# Page_B_SignalInput.net
KiCad netlist of a schematic drawn in Altium Designer
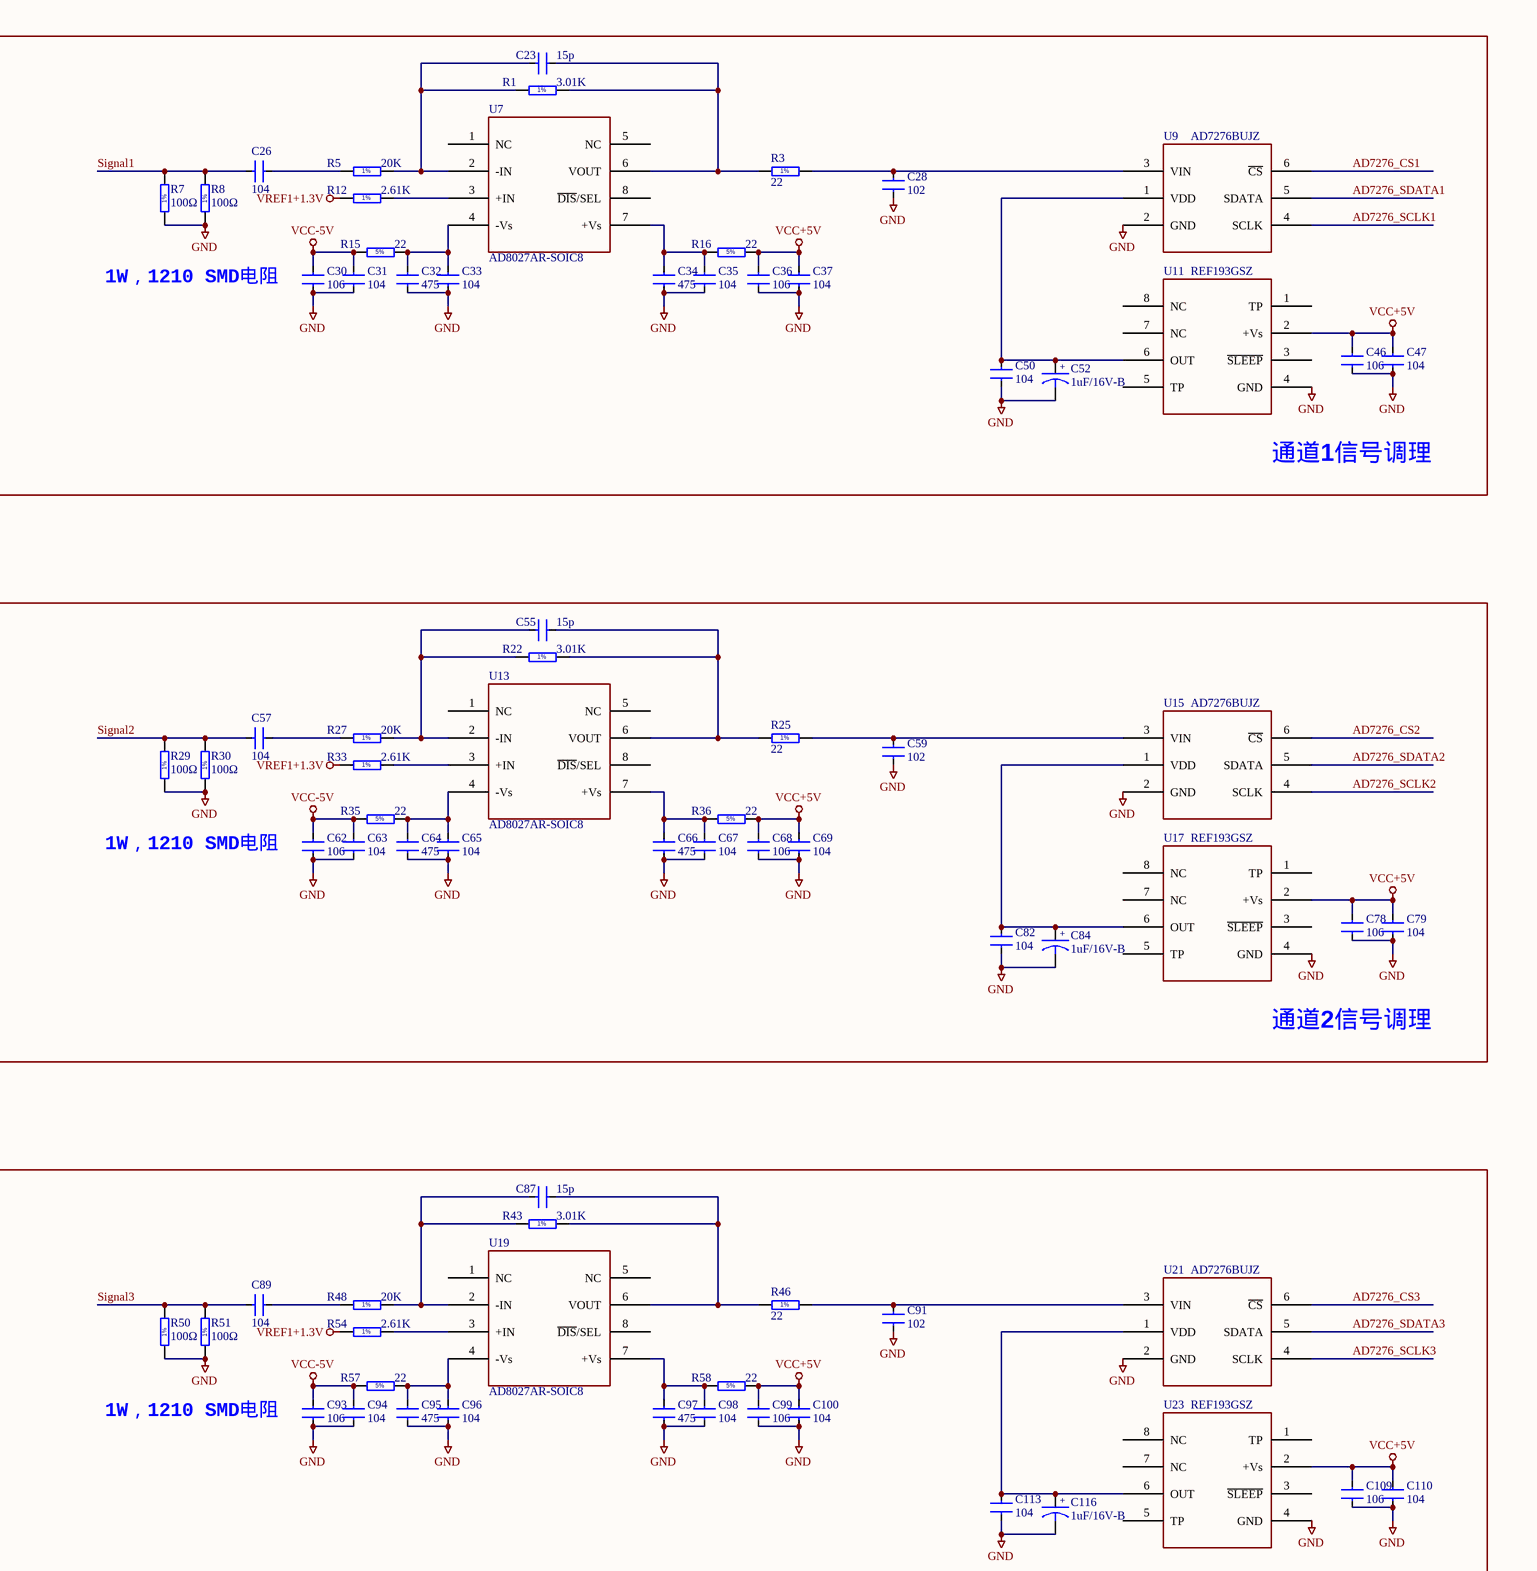
[diagram p0: Page B_SignalInput.SchDoc, top left]
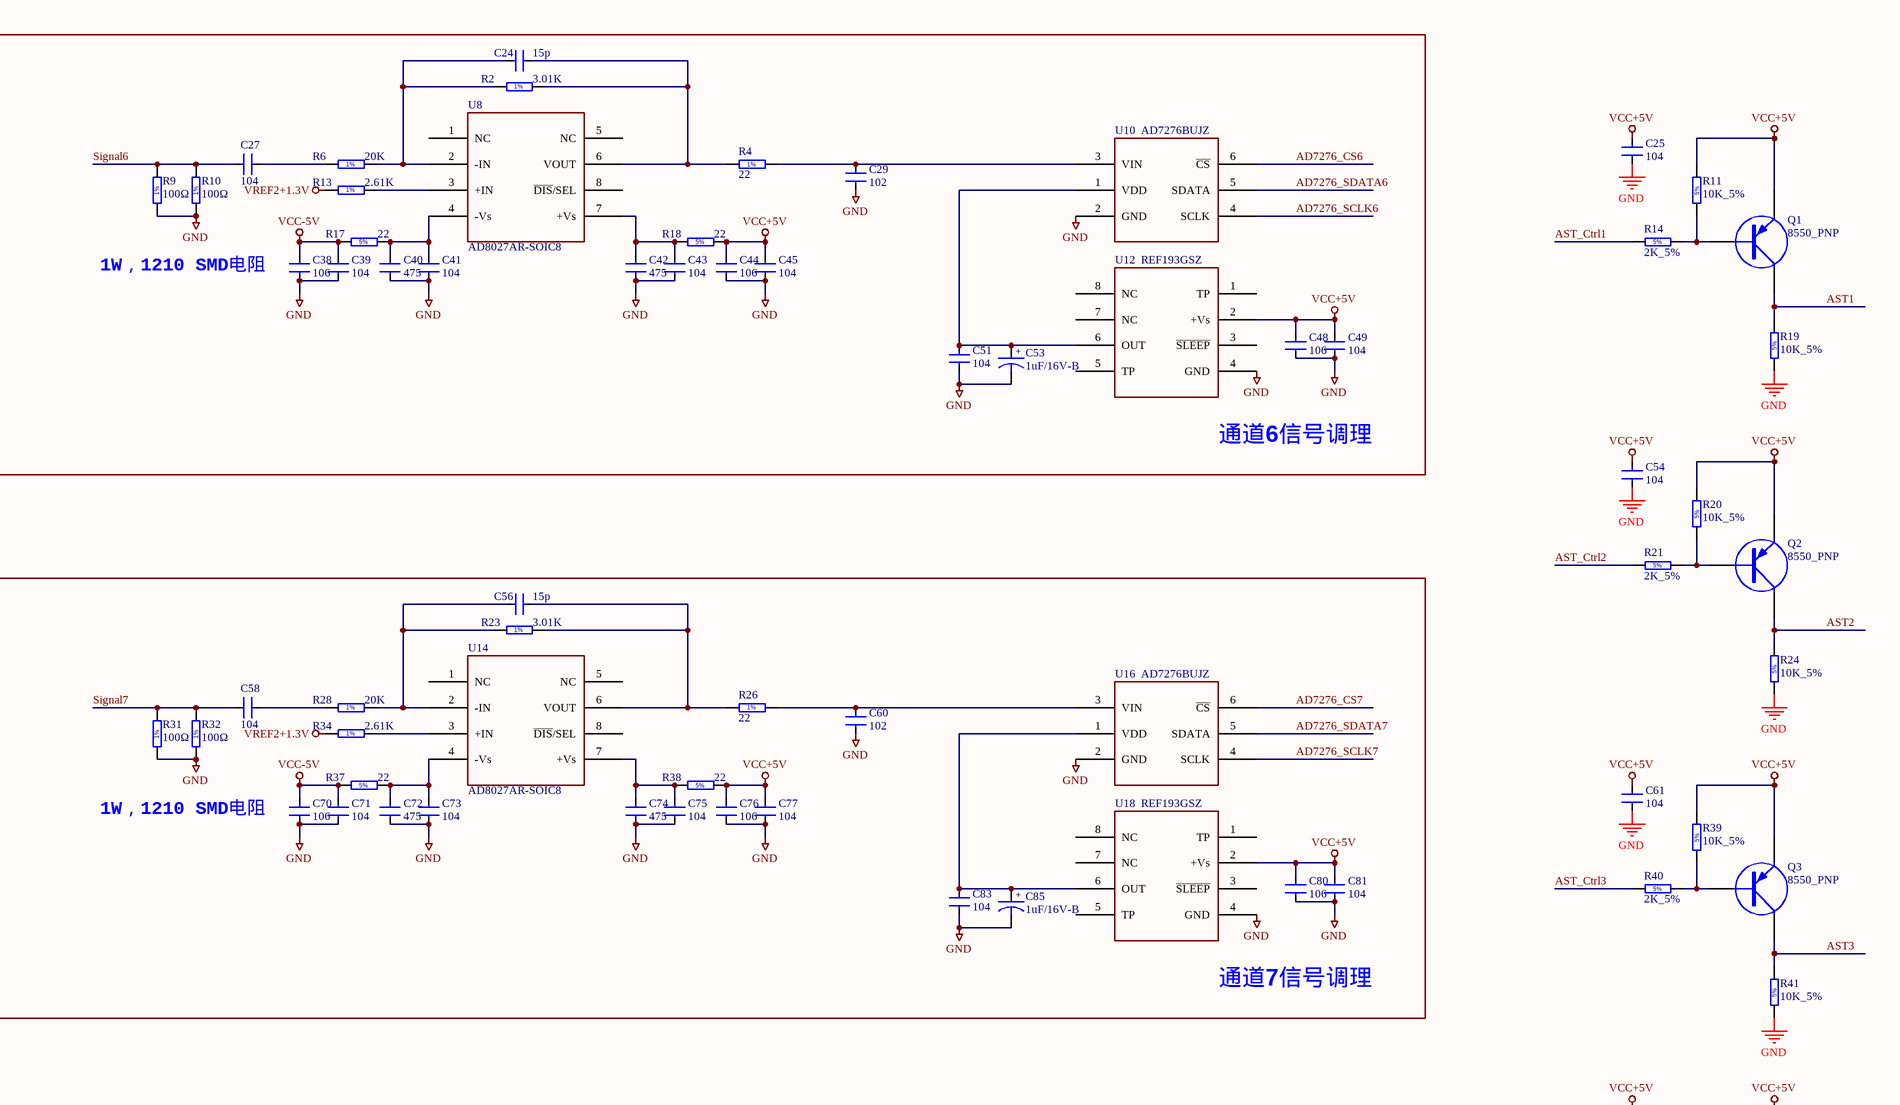
[diagram p1: Page B_SignalInput.SchDoc, top right]
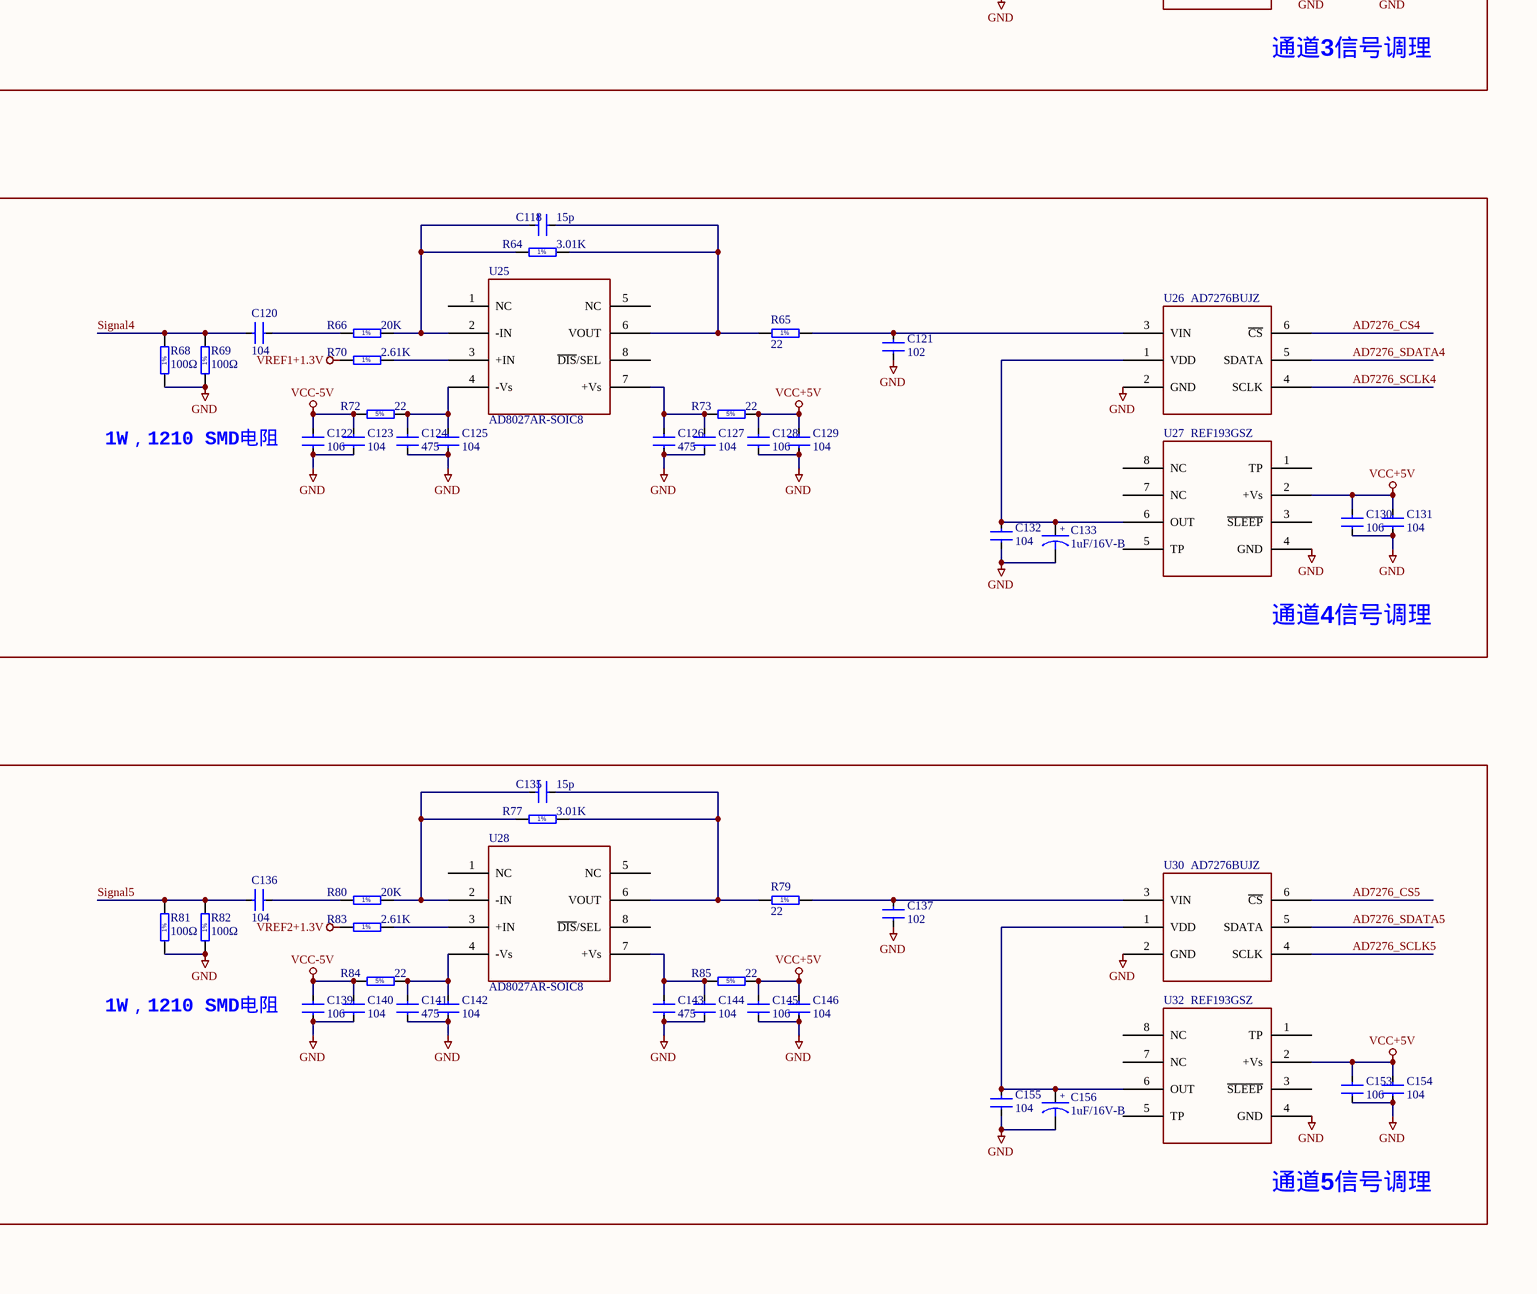
[diagram p2: Page B_SignalInput.SchDoc, bottom left]
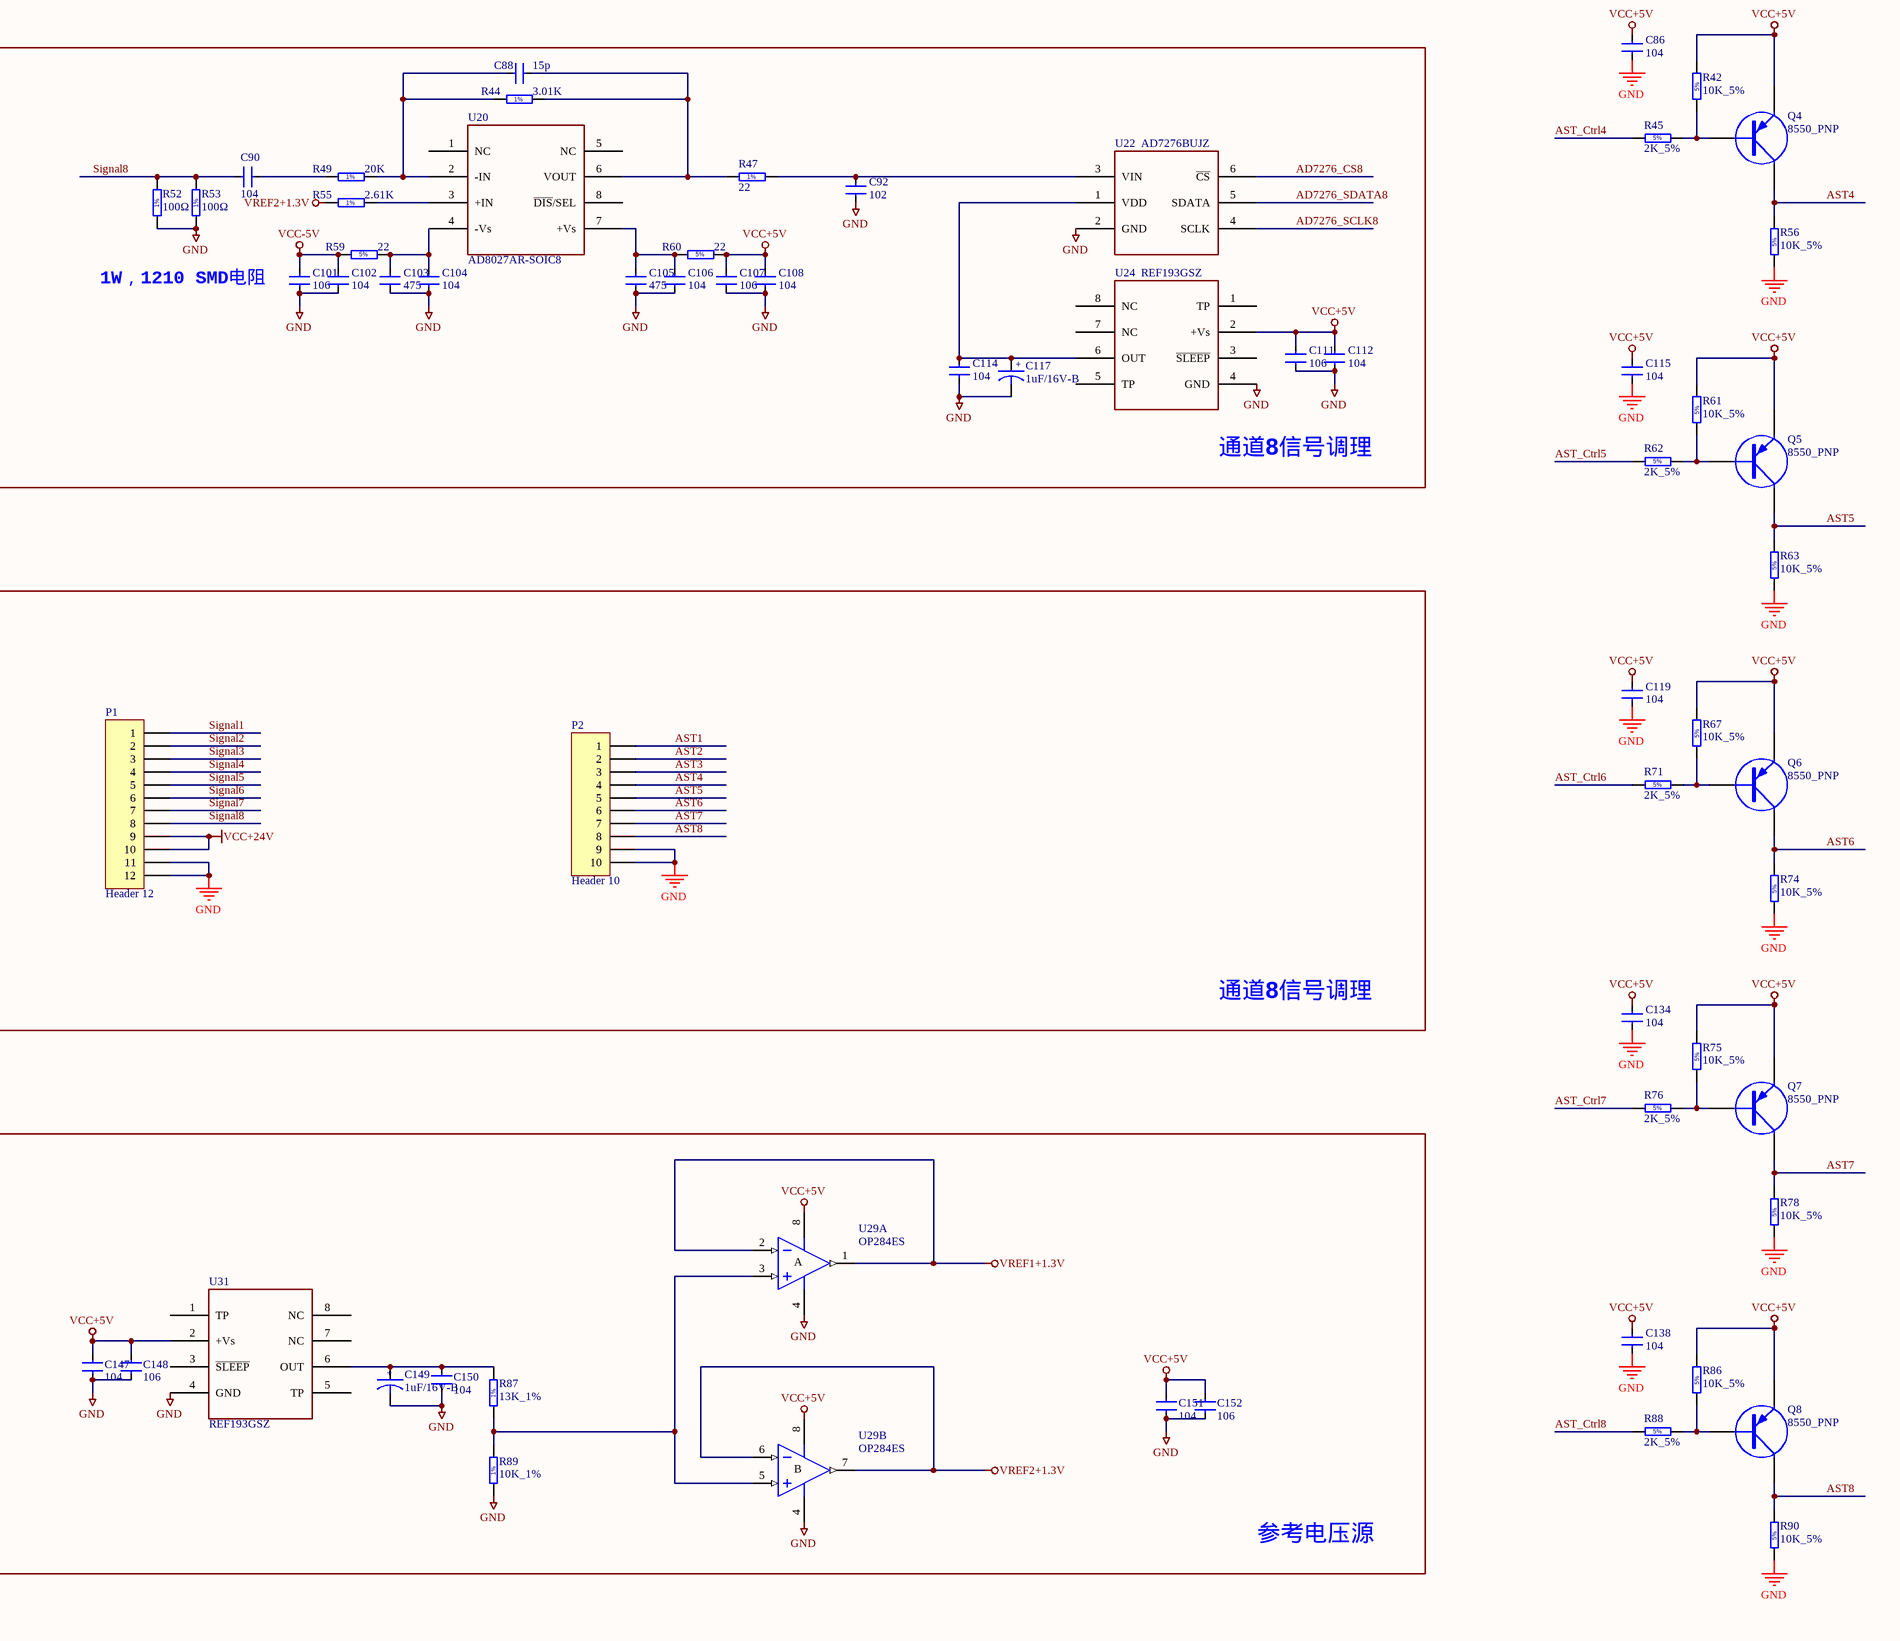
[diagram p3: Page B_SignalInput.SchDoc, bottom right]

(export (version "E")
  (design (tool "Eeschema 10.0.6"))
  (components
    (comp (ref "C23")
      (value "15p")
      (footprint "0603C")
      (description "C-X5R/X7R")
      (libsource (lib "贴片电阻电容") (part "C-X5R/X7R"))
    )
    (comp (ref "C24")
      (value "15p")
      (footprint "0603C")
      (description "C-X5R/X7R")
      (libsource (lib "贴片电阻电容") (part "C-X5R/X7R"))
    )
    (comp (ref "C25")
      (value "104")
      (footprint "0603C")
      (description "C-X5R/X7R")
      (libsource (lib "贴片电阻电容") (part "C-X5R/X7R"))
    )
    (comp (ref "C26")
      (value "104")
      (footprint "0603C")
      (description "C-X5R/X7R")
      (libsource (lib "贴片电阻电容") (part "C-X5R/X7R"))
    )
    (comp (ref "C27")
      (value "104")
      (footprint "0603C")
      (description "C-X5R/X7R")
      (libsource (lib "贴片电阻电容") (part "C-X5R/X7R"))
    )
    (comp (ref "C28")
      (value "102")
      (footprint "0603C")
      (description "C-X5R/X7R")
      (libsource (lib "贴片电阻电容") (part "C-X5R/X7R"))
    )
    (comp (ref "C29")
      (value "102")
      (footprint "0603C")
      (description "C-X5R/X7R")
      (libsource (lib "贴片电阻电容") (part "C-X5R/X7R"))
    )
    (comp (ref "C30")
      (value "106")
      (footprint "0603C")
      (description "C-X5R/X7R")
      (libsource (lib "贴片电阻电容") (part "C-X5R/X7R"))
    )
    (comp (ref "C31")
      (value "104")
      (footprint "0603C")
      (description "C-X5R/X7R")
      (libsource (lib "贴片电阻电容") (part "C-X5R/X7R"))
    )
    (comp (ref "C32")
      (value "475")
      (footprint "0603C")
      (description "C-X5R/X7R")
      (libsource (lib "贴片电阻电容") (part "C-X5R/X7R"))
    )
    (comp (ref "C33")
      (value "104")
      (footprint "0603C")
      (description "C-X5R/X7R")
      (libsource (lib "贴片电阻电容") (part "C-X5R/X7R"))
    )
    (comp (ref "C34")
      (value "475")
      (footprint "0603C")
      (description "C-X5R/X7R")
      (libsource (lib "贴片电阻电容") (part "C-X5R/X7R"))
    )
    (comp (ref "C35")
      (value "104")
      (footprint "0603C")
      (description "C-X5R/X7R")
      (libsource (lib "贴片电阻电容") (part "C-X5R/X7R"))
    )
    (comp (ref "C36")
      (value "106")
      (footprint "0603C")
      (description "C-X5R/X7R")
      (libsource (lib "贴片电阻电容") (part "C-X5R/X7R"))
    )
    (comp (ref "C37")
      (value "104")
      (footprint "0603C")
      (description "C-X5R/X7R")
      (libsource (lib "贴片电阻电容") (part "C-X5R/X7R"))
    )
    (comp (ref "C38")
      (value "106")
      (footprint "0603C")
      (description "C-X5R/X7R")
      (libsource (lib "贴片电阻电容") (part "C-X5R/X7R"))
    )
    (comp (ref "C39")
      (value "104")
      (footprint "0603C")
      (description "C-X5R/X7R")
      (libsource (lib "贴片电阻电容") (part "C-X5R/X7R"))
    )
    (comp (ref "C40")
      (value "475")
      (footprint "0603C")
      (description "C-X5R/X7R")
      (libsource (lib "贴片电阻电容") (part "C-X5R/X7R"))
    )
    (comp (ref "C41")
      (value "104")
      (footprint "0603C")
      (description "C-X5R/X7R")
      (libsource (lib "贴片电阻电容") (part "C-X5R/X7R"))
    )
    (comp (ref "C42")
      (value "475")
      (footprint "0603C")
      (description "C-X5R/X7R")
      (libsource (lib "贴片电阻电容") (part "C-X5R/X7R"))
    )
    (comp (ref "C43")
      (value "104")
      (footprint "0603C")
      (description "C-X5R/X7R")
      (libsource (lib "贴片电阻电容") (part "C-X5R/X7R"))
    )
    (comp (ref "C44")
      (value "106")
      (footprint "0603C")
      (description "C-X5R/X7R")
      (libsource (lib "贴片电阻电容") (part "C-X5R/X7R"))
    )
    (comp (ref "C45")
      (value "104")
      (footprint "0603C")
      (description "C-X5R/X7R")
      (libsource (lib "贴片电阻电容") (part "C-X5R/X7R"))
    )
    (comp (ref "C46")
      (value "106")
      (footprint "0603C")
      (description "C-X5R/X7R")
      (libsource (lib "贴片电阻电容") (part "C-X5R/X7R"))
    )
    (comp (ref "C47")
      (value "104")
      (footprint "0603C")
      (description "C-X5R/X7R")
      (libsource (lib "贴片电阻电容") (part "C-X5R/X7R"))
    )
    (comp (ref "C48")
      (value "106")
      (footprint "0603C")
      (description "C-X5R/X7R")
      (libsource (lib "贴片电阻电容") (part "C-X5R/X7R"))
    )
    (comp (ref "C49")
      (value "104")
      (footprint "0603C")
      (description "C-X5R/X7R")
      (libsource (lib "贴片电阻电容") (part "C-X5R/X7R"))
    )
    (comp (ref "C50")
      (value "104")
      (footprint "0603C")
      (description "C-X5R/X7R")
      (libsource (lib "贴片电阻电容") (part "C-X5R/X7R"))
    )
    (comp (ref "C51")
      (value "104")
      (footprint "0603C")
      (description "C-X5R/X7R")
      (libsource (lib "贴片电阻电容") (part "C-X5R/X7R"))
    )
    (comp (ref "C52") (value "1uF/16V-B") (footprint "TCC-B") (libsource (lib "钽电容") (part "10uF/16V-B")))
    (comp (ref "C53") (value "1uF/16V-B") (footprint "TCC-B") (libsource (lib "钽电容") (part "10uF/16V-B")))
    (comp (ref "C54")
      (value "104")
      (footprint "0603C")
      (description "C-X5R/X7R")
      (libsource (lib "贴片电阻电容") (part "C-X5R/X7R"))
    )
    (comp (ref "C55")
      (value "15p")
      (footprint "0603C")
      (description "C-X5R/X7R")
      (libsource (lib "贴片电阻电容") (part "C-X5R/X7R"))
    )
    (comp (ref "C56")
      (value "15p")
      (footprint "0603C")
      (description "C-X5R/X7R")
      (libsource (lib "贴片电阻电容") (part "C-X5R/X7R"))
    )
    (comp (ref "C57")
      (value "104")
      (footprint "0603C")
      (description "C-X5R/X7R")
      (libsource (lib "贴片电阻电容") (part "C-X5R/X7R"))
    )
    (comp (ref "C58")
      (value "104")
      (footprint "0603C")
      (description "C-X5R/X7R")
      (libsource (lib "贴片电阻电容") (part "C-X5R/X7R"))
    )
    (comp (ref "C59")
      (value "102")
      (footprint "0603C")
      (description "C-X5R/X7R")
      (libsource (lib "贴片电阻电容") (part "C-X5R/X7R"))
    )
    (comp (ref "C60")
      (value "102")
      (footprint "0603C")
      (description "C-X5R/X7R")
      (libsource (lib "贴片电阻电容") (part "C-X5R/X7R"))
    )
    (comp (ref "C61")
      (value "104")
      (footprint "0603C")
      (description "C-X5R/X7R")
      (libsource (lib "贴片电阻电容") (part "C-X5R/X7R"))
    )
    (comp (ref "C62")
      (value "106")
      (footprint "0603C")
      (description "C-X5R/X7R")
      (libsource (lib "贴片电阻电容") (part "C-X5R/X7R"))
    )
    (comp (ref "C63")
      (value "104")
      (footprint "0603C")
      (description "C-X5R/X7R")
      (libsource (lib "贴片电阻电容") (part "C-X5R/X7R"))
    )
    (comp (ref "C64")
      (value "475")
      (footprint "0603C")
      (description "C-X5R/X7R")
      (libsource (lib "贴片电阻电容") (part "C-X5R/X7R"))
    )
    (comp (ref "C65")
      (value "104")
      (footprint "0603C")
      (description "C-X5R/X7R")
      (libsource (lib "贴片电阻电容") (part "C-X5R/X7R"))
    )
    (comp (ref "C66")
      (value "475")
      (footprint "0603C")
      (description "C-X5R/X7R")
      (libsource (lib "贴片电阻电容") (part "C-X5R/X7R"))
    )
    (comp (ref "C67")
      (value "104")
      (footprint "0603C")
      (description "C-X5R/X7R")
      (libsource (lib "贴片电阻电容") (part "C-X5R/X7R"))
    )
    (comp (ref "C68")
      (value "106")
      (footprint "0603C")
      (description "C-X5R/X7R")
      (libsource (lib "贴片电阻电容") (part "C-X5R/X7R"))
    )
    (comp (ref "C69")
      (value "104")
      (footprint "0603C")
      (description "C-X5R/X7R")
      (libsource (lib "贴片电阻电容") (part "C-X5R/X7R"))
    )
    (comp (ref "C70")
      (value "106")
      (footprint "0603C")
      (description "C-X5R/X7R")
      (libsource (lib "贴片电阻电容") (part "C-X5R/X7R"))
    )
    (comp (ref "C71")
      (value "104")
      (footprint "0603C")
      (description "C-X5R/X7R")
      (libsource (lib "贴片电阻电容") (part "C-X5R/X7R"))
    )
    (comp (ref "C72")
      (value "475")
      (footprint "0603C")
      (description "C-X5R/X7R")
      (libsource (lib "贴片电阻电容") (part "C-X5R/X7R"))
    )
    (comp (ref "C73")
      (value "104")
      (footprint "0603C")
      (description "C-X5R/X7R")
      (libsource (lib "贴片电阻电容") (part "C-X5R/X7R"))
    )
    (comp (ref "C74")
      (value "475")
      (footprint "0603C")
      (description "C-X5R/X7R")
      (libsource (lib "贴片电阻电容") (part "C-X5R/X7R"))
    )
    (comp (ref "C75")
      (value "104")
      (footprint "0603C")
      (description "C-X5R/X7R")
      (libsource (lib "贴片电阻电容") (part "C-X5R/X7R"))
    )
    (comp (ref "C76")
      (value "106")
      (footprint "0603C")
      (description "C-X5R/X7R")
      (libsource (lib "贴片电阻电容") (part "C-X5R/X7R"))
    )
    (comp (ref "C77")
      (value "104")
      (footprint "0603C")
      (description "C-X5R/X7R")
      (libsource (lib "贴片电阻电容") (part "C-X5R/X7R"))
    )
    (comp (ref "C78")
      (value "106")
      (footprint "0603C")
      (description "C-X5R/X7R")
      (libsource (lib "贴片电阻电容") (part "C-X5R/X7R"))
    )
    (comp (ref "C79")
      (value "104")
      (footprint "0603C")
      (description "C-X5R/X7R")
      (libsource (lib "贴片电阻电容") (part "C-X5R/X7R"))
    )
    (comp (ref "C80")
      (value "106")
      (footprint "0603C")
      (description "C-X5R/X7R")
      (libsource (lib "贴片电阻电容") (part "C-X5R/X7R"))
    )
    (comp (ref "C81")
      (value "104")
      (footprint "0603C")
      (description "C-X5R/X7R")
      (libsource (lib "贴片电阻电容") (part "C-X5R/X7R"))
    )
    (comp (ref "C82")
      (value "104")
      (footprint "0603C")
      (description "C-X5R/X7R")
      (libsource (lib "贴片电阻电容") (part "C-X5R/X7R"))
    )
    (comp (ref "C83")
      (value "104")
      (footprint "0603C")
      (description "C-X5R/X7R")
      (libsource (lib "贴片电阻电容") (part "C-X5R/X7R"))
    )
    (comp (ref "C84") (value "1uF/16V-B") (footprint "TCC-B") (libsource (lib "钽电容") (part "10uF/16V-B")))
    (comp (ref "C85") (value "1uF/16V-B") (footprint "TCC-B") (libsource (lib "钽电容") (part "10uF/16V-B")))
    (comp (ref "C86")
      (value "104")
      (footprint "0603C")
      (description "C-X5R/X7R")
      (libsource (lib "贴片电阻电容") (part "C-X5R/X7R"))
    )
    (comp (ref "C87")
      (value "15p")
      (footprint "0603C")
      (description "C-X5R/X7R")
      (libsource (lib "贴片电阻电容") (part "C-X5R/X7R"))
    )
    (comp (ref "C88")
      (value "15p")
      (footprint "0603C")
      (description "C-X5R/X7R")
      (libsource (lib "贴片电阻电容") (part "C-X5R/X7R"))
    )
    (comp (ref "C89")
      (value "104")
      (footprint "0603C")
      (description "C-X5R/X7R")
      (libsource (lib "贴片电阻电容") (part "C-X5R/X7R"))
    )
    (comp (ref "C90")
      (value "104")
      (footprint "0603C")
      (description "C-X5R/X7R")
      (libsource (lib "贴片电阻电容") (part "C-X5R/X7R"))
    )
    (comp (ref "C91")
      (value "102")
      (footprint "0603C")
      (description "C-X5R/X7R")
      (libsource (lib "贴片电阻电容") (part "C-X5R/X7R"))
    )
    (comp (ref "C92")
      (value "102")
      (footprint "0603C")
      (description "C-X5R/X7R")
      (libsource (lib "贴片电阻电容") (part "C-X5R/X7R"))
    )
    (comp (ref "C93")
      (value "106")
      (footprint "0603C")
      (description "C-X5R/X7R")
      (libsource (lib "贴片电阻电容") (part "C-X5R/X7R"))
    )
    (comp (ref "C94")
      (value "104")
      (footprint "0603C")
      (description "C-X5R/X7R")
      (libsource (lib "贴片电阻电容") (part "C-X5R/X7R"))
    )
    (comp (ref "C95")
      (value "475")
      (footprint "0603C")
      (description "C-X5R/X7R")
      (libsource (lib "贴片电阻电容") (part "C-X5R/X7R"))
    )
    (comp (ref "C96")
      (value "104")
      (footprint "0603C")
      (description "C-X5R/X7R")
      (libsource (lib "贴片电阻电容") (part "C-X5R/X7R"))
    )
    (comp (ref "C97")
      (value "475")
      (footprint "0603C")
      (description "C-X5R/X7R")
      (libsource (lib "贴片电阻电容") (part "C-X5R/X7R"))
    )
    (comp (ref "C98")
      (value "104")
      (footprint "0603C")
      (description "C-X5R/X7R")
      (libsource (lib "贴片电阻电容") (part "C-X5R/X7R"))
    )
    (comp (ref "C99")
      (value "106")
      (footprint "0603C")
      (description "C-X5R/X7R")
      (libsource (lib "贴片电阻电容") (part "C-X5R/X7R"))
    )
    (comp (ref "C100")
      (value "104")
      (footprint "0603C")
      (description "C-X5R/X7R")
      (libsource (lib "贴片电阻电容") (part "C-X5R/X7R"))
    )
    (comp (ref "C101")
      (value "106")
      (footprint "0603C")
      (description "C-X5R/X7R")
      (libsource (lib "贴片电阻电容") (part "C-X5R/X7R"))
    )
    (comp (ref "C102")
      (value "104")
      (footprint "0603C")
      (description "C-X5R/X7R")
      (libsource (lib "贴片电阻电容") (part "C-X5R/X7R"))
    )
    (comp (ref "C103")
      (value "475")
      (footprint "0603C")
      (description "C-X5R/X7R")
      (libsource (lib "贴片电阻电容") (part "C-X5R/X7R"))
    )
    (comp (ref "C104")
      (value "104")
      (footprint "0603C")
      (description "C-X5R/X7R")
      (libsource (lib "贴片电阻电容") (part "C-X5R/X7R"))
    )
    (comp (ref "C105")
      (value "475")
      (footprint "0603C")
      (description "C-X5R/X7R")
      (libsource (lib "贴片电阻电容") (part "C-X5R/X7R"))
    )
    (comp (ref "C106")
      (value "104")
      (footprint "0603C")
      (description "C-X5R/X7R")
      (libsource (lib "贴片电阻电容") (part "C-X5R/X7R"))
    )
    (comp (ref "C107")
      (value "106")
      (footprint "0603C")
      (description "C-X5R/X7R")
      (libsource (lib "贴片电阻电容") (part "C-X5R/X7R"))
    )
    (comp (ref "C108")
      (value "104")
      (footprint "0603C")
      (description "C-X5R/X7R")
      (libsource (lib "贴片电阻电容") (part "C-X5R/X7R"))
    )
    (comp (ref "C109")
      (value "106")
      (footprint "0603C")
      (description "C-X5R/X7R")
      (libsource (lib "贴片电阻电容") (part "C-X5R/X7R"))
    )
    (comp (ref "C110")
      (value "104")
      (footprint "0603C")
      (description "C-X5R/X7R")
      (libsource (lib "贴片电阻电容") (part "C-X5R/X7R"))
    )
    (comp (ref "C111")
      (value "106")
      (footprint "0603C")
      (description "C-X5R/X7R")
      (libsource (lib "贴片电阻电容") (part "C-X5R/X7R"))
    )
    (comp (ref "C112")
      (value "104")
      (footprint "0603C")
      (description "C-X5R/X7R")
      (libsource (lib "贴片电阻电容") (part "C-X5R/X7R"))
    )
    (comp (ref "C113")
      (value "104")
      (footprint "0603C")
      (description "C-X5R/X7R")
      (libsource (lib "贴片电阻电容") (part "C-X5R/X7R"))
    )
    (comp (ref "C114")
      (value "104")
      (footprint "0603C")
      (description "C-X5R/X7R")
      (libsource (lib "贴片电阻电容") (part "C-X5R/X7R"))
    )
    (comp (ref "C115")
      (value "104")
      (footprint "0603C")
      (description "C-X5R/X7R")
      (libsource (lib "贴片电阻电容") (part "C-X5R/X7R"))
    )
    (comp (ref "C116") (value "1uF/16V-B") (footprint "TCC-B") (libsource (lib "钽电容") (part "10uF/16V-B")))
    (comp (ref "C117") (value "1uF/16V-B") (footprint "TCC-B") (libsource (lib "钽电容") (part "10uF/16V-B")))
    (comp (ref "C118")
      (value "15p")
      (footprint "0603C")
      (description "C-X5R/X7R")
      (libsource (lib "贴片电阻电容") (part "C-X5R/X7R"))
    )
    (comp (ref "C119")
      (value "104")
      (footprint "0603C")
      (description "C-X5R/X7R")
      (libsource (lib "贴片电阻电容") (part "C-X5R/X7R"))
    )
    (comp (ref "C120")
      (value "104")
      (footprint "0603C")
      (description "C-X5R/X7R")
      (libsource (lib "贴片电阻电容") (part "C-X5R/X7R"))
    )
    (comp (ref "C121")
      (value "102")
      (footprint "0603C")
      (description "C-X5R/X7R")
      (libsource (lib "贴片电阻电容") (part "C-X5R/X7R"))
    )
    (comp (ref "C122")
      (value "106")
      (footprint "0603C")
      (description "C-X5R/X7R")
      (libsource (lib "贴片电阻电容") (part "C-X5R/X7R"))
    )
    (comp (ref "C123")
      (value "104")
      (footprint "0603C")
      (description "C-X5R/X7R")
      (libsource (lib "贴片电阻电容") (part "C-X5R/X7R"))
    )
    (comp (ref "C124")
      (value "475")
      (footprint "0603C")
      (description "C-X5R/X7R")
      (libsource (lib "贴片电阻电容") (part "C-X5R/X7R"))
    )
    (comp (ref "C125")
      (value "104")
      (footprint "0603C")
      (description "C-X5R/X7R")
      (libsource (lib "贴片电阻电容") (part "C-X5R/X7R"))
    )
    (comp (ref "C126")
      (value "475")
      (footprint "0603C")
      (description "C-X5R/X7R")
      (libsource (lib "贴片电阻电容") (part "C-X5R/X7R"))
    )
    (comp (ref "C127")
      (value "104")
      (footprint "0603C")
      (description "C-X5R/X7R")
      (libsource (lib "贴片电阻电容") (part "C-X5R/X7R"))
    )
    (comp (ref "C128")
      (value "106")
      (footprint "0603C")
      (description "C-X5R/X7R")
      (libsource (lib "贴片电阻电容") (part "C-X5R/X7R"))
    )
    (comp (ref "C129")
      (value "104")
      (footprint "0603C")
      (description "C-X5R/X7R")
      (libsource (lib "贴片电阻电容") (part "C-X5R/X7R"))
    )
    (comp (ref "C130")
      (value "106")
      (footprint "0603C")
      (description "C-X5R/X7R")
      (libsource (lib "贴片电阻电容") (part "C-X5R/X7R"))
    )
    (comp (ref "C131")
      (value "104")
      (footprint "0603C")
      (description "C-X5R/X7R")
      (libsource (lib "贴片电阻电容") (part "C-X5R/X7R"))
    )
    (comp (ref "C132")
      (value "104")
      (footprint "0603C")
      (description "C-X5R/X7R")
      (libsource (lib "贴片电阻电容") (part "C-X5R/X7R"))
    )
    (comp (ref "C133") (value "1uF/16V-B") (footprint "TCC-B") (libsource (lib "钽电容") (part "10uF/16V-B")))
    (comp (ref "C134")
      (value "104")
      (footprint "0603C")
      (description "C-X5R/X7R")
      (libsource (lib "贴片电阻电容") (part "C-X5R/X7R"))
    )
    (comp (ref "C135")
      (value "15p")
      (footprint "0603C")
      (description "C-X5R/X7R")
      (libsource (lib "贴片电阻电容") (part "C-X5R/X7R"))
    )
    (comp (ref "C136")
      (value "104")
      (footprint "0603C")
      (description "C-X5R/X7R")
      (libsource (lib "贴片电阻电容") (part "C-X5R/X7R"))
    )
    (comp (ref "C137")
      (value "102")
      (footprint "0603C")
      (description "C-X5R/X7R")
      (libsource (lib "贴片电阻电容") (part "C-X5R/X7R"))
    )
    (comp (ref "C138")
      (value "104")
      (footprint "0603C")
      (description "C-X5R/X7R")
      (libsource (lib "贴片电阻电容") (part "C-X5R/X7R"))
    )
    (comp (ref "C139")
      (value "106")
      (footprint "0603C")
      (description "C-X5R/X7R")
      (libsource (lib "贴片电阻电容") (part "C-X5R/X7R"))
    )
    (comp (ref "C140")
      (value "104")
      (footprint "0603C")
      (description "C-X5R/X7R")
      (libsource (lib "贴片电阻电容") (part "C-X5R/X7R"))
    )
    (comp (ref "C141")
      (value "475")
      (footprint "0603C")
      (description "C-X5R/X7R")
      (libsource (lib "贴片电阻电容") (part "C-X5R/X7R"))
    )
    (comp (ref "C142")
      (value "104")
      (footprint "0603C")
      (description "C-X5R/X7R")
      (libsource (lib "贴片电阻电容") (part "C-X5R/X7R"))
    )
    (comp (ref "C143")
      (value "475")
      (footprint "0603C")
      (description "C-X5R/X7R")
      (libsource (lib "贴片电阻电容") (part "C-X5R/X7R"))
    )
    (comp (ref "C144")
      (value "104")
      (footprint "0603C")
      (description "C-X5R/X7R")
      (libsource (lib "贴片电阻电容") (part "C-X5R/X7R"))
    )
    (comp (ref "C145")
      (value "106")
      (footprint "0603C")
      (description "C-X5R/X7R")
      (libsource (lib "贴片电阻电容") (part "C-X5R/X7R"))
    )
    (comp (ref "C146")
      (value "104")
      (footprint "0603C")
      (description "C-X5R/X7R")
      (libsource (lib "贴片电阻电容") (part "C-X5R/X7R"))
    )
    (comp (ref "C147")
      (value "104")
      (footprint "0603C")
      (description "C-X5R/X7R")
      (libsource (lib "贴片电阻电容") (part "C-X5R/X7R"))
    )
    (comp (ref "C148")
      (value "106")
      (footprint "0603C")
      (description "C-X5R/X7R")
      (libsource (lib "贴片电阻电容") (part "C-X5R/X7R"))
    )
    (comp (ref "C149") (value "1uF/16V-B") (footprint "TCC-B") (libsource (lib "") (part "10uF/16V-B_1")))
    (comp (ref "C150")
      (value "104")
      (footprint "0603C")
      (description "C-X5R/X7R")
      (libsource (lib "贴片电阻电容") (part "C-X5R/X7R"))
    )
    (comp (ref "C151")
      (value "104")
      (footprint "0603C")
      (description "C-X5R/X7R")
      (libsource (lib "贴片电阻电容") (part "C-X5R/X7R"))
    )
    (comp (ref "C152")
      (value "106")
      (footprint "0603C")
      (description "C-X5R/X7R")
      (libsource (lib "贴片电阻电容") (part "C-X5R/X7R"))
    )
    (comp (ref "C153")
      (value "106")
      (footprint "0603C")
      (description "C-X5R/X7R")
      (libsource (lib "贴片电阻电容") (part "C-X5R/X7R"))
    )
    (comp (ref "C154")
      (value "104")
      (footprint "0603C")
      (description "C-X5R/X7R")
      (libsource (lib "贴片电阻电容") (part "C-X5R/X7R"))
    )
    (comp (ref "C155")
      (value "104")
      (footprint "0603C")
      (description "C-X5R/X7R")
      (libsource (lib "贴片电阻电容") (part "C-X5R/X7R"))
    )
    (comp (ref "C156") (value "1uF/16V-B") (footprint "TCC-B") (libsource (lib "钽电容") (part "10uF/16V-B")))
    (comp (ref "P1")
      (value "Header 12")
      (footprint "CHAZUO12*2.54")
      (description "Header, 12-Pin")
      (fields (field (name "PUBLISHER") "Altium Limited"))
      (libsource (lib "Miscellaneous Connectors") (part "Header 12"))
    )
    (comp (ref "P2")
      (value "Header 10")
      (footprint "CHAZUO10*2.54")
      (description "Header, 10-Pin")
      (fields (field (name "PUBLISHER") "Altium Limited"))
      (libsource (lib "Miscellaneous Connectors") (part "Header 10"))
    )
    (comp (ref "Q1")
      (value "8550_PNP")
      (footprint "SOT-23")
      (description "PNP Transistor")
      (libsource (lib "Miscellaneous Devices") (part "PNP"))
    )
    (comp (ref "Q2")
      (value "8550_PNP")
      (footprint "SOT-23")
      (description "PNP Transistor")
      (libsource (lib "Miscellaneous Devices") (part "PNP"))
    )
    (comp (ref "Q3")
      (value "8550_PNP")
      (footprint "SOT-23")
      (description "PNP Transistor")
      (libsource (lib "Miscellaneous Devices") (part "PNP"))
    )
    (comp (ref "Q4")
      (value "8550_PNP")
      (footprint "SOT-23")
      (description "PNP Transistor")
      (libsource (lib "Miscellaneous Devices") (part "PNP"))
    )
    (comp (ref "Q5")
      (value "8550_PNP")
      (footprint "SOT-23")
      (description "PNP Transistor")
      (libsource (lib "Miscellaneous Devices") (part "PNP"))
    )
    (comp (ref "Q6")
      (value "8550_PNP")
      (footprint "SOT-23")
      (description "PNP Transistor")
      (libsource (lib "Miscellaneous Devices") (part "PNP"))
    )
    (comp (ref "Q7")
      (value "8550_PNP")
      (footprint "SOT-23")
      (description "PNP Transistor")
      (libsource (lib "Miscellaneous Devices") (part "PNP"))
    )
    (comp (ref "Q8")
      (value "8550_PNP")
      (footprint "SOT-23")
      (description "PNP Transistor")
      (libsource (lib "Miscellaneous Devices") (part "PNP"))
    )
    (comp (ref "R1")
      (value "3.01K")
      (footprint "0603R")
      (description "Resistor - 1%")
      (libsource (lib "贴片电阻电容") (part "Resistor - 1%"))
    )
    (comp (ref "R2")
      (value "3.01K")
      (footprint "0603R")
      (description "Resistor - 1%")
      (libsource (lib "贴片电阻电容") (part "Resistor - 1%"))
    )
    (comp (ref "R3")
      (value "22")
      (footprint "0603R")
      (description "Resistor - 1%")
      (libsource (lib "贴片电阻电容") (part "Resistor - 1%"))
    )
    (comp (ref "R4")
      (value "22")
      (footprint "0603R")
      (description "Resistor - 1%")
      (libsource (lib "贴片电阻电容") (part "Resistor - 1%"))
    )
    (comp (ref "R5")
      (value "20K")
      (footprint "0603R")
      (description "Resistor - 1%")
      (libsource (lib "贴片电阻电容") (part "Resistor - 1%"))
    )
    (comp (ref "R6")
      (value "20K")
      (footprint "0603R")
      (description "Resistor - 1%")
      (libsource (lib "贴片电阻电容") (part "Resistor - 1%"))
    )
    (comp (ref "R7")
      (value "100Ω")
      (footprint "1210")
      (description "Resistor - 1%")
      (libsource (lib "贴片电阻电容") (part "Resistor - 1%"))
    )
    (comp (ref "R8")
      (value "100Ω")
      (footprint "1210")
      (description "Resistor - 1%")
      (libsource (lib "贴片电阻电容") (part "Resistor - 1%"))
    )
    (comp (ref "R9")
      (value "100Ω")
      (footprint "1210")
      (description "Resistor - 1%")
      (libsource (lib "贴片电阻电容") (part "Resistor - 1%"))
    )
    (comp (ref "R10")
      (value "100Ω")
      (footprint "1210")
      (description "Resistor - 1%")
      (libsource (lib "贴片电阻电容") (part "Resistor - 1%"))
    )
    (comp (ref "R11")
      (value "10K_5%")
      (footprint "0603R")
      (description "Resistor - 5%")
      (libsource (lib "贴片电阻电容") (part "Resistor - 5%"))
    )
    (comp (ref "R12")
      (value "2.61K")
      (footprint "0603R")
      (description "Resistor - 1%")
      (libsource (lib "贴片电阻电容") (part "Resistor - 1%"))
    )
    (comp (ref "R13")
      (value "2.61K")
      (footprint "0603R")
      (description "Resistor - 1%")
      (libsource (lib "贴片电阻电容") (part "Resistor - 1%"))
    )
    (comp (ref "R14")
      (value "2K_5%")
      (footprint "0603R")
      (description "Resistor - 5%")
      (libsource (lib "贴片电阻电容") (part "Resistor - 5%"))
    )
    (comp (ref "R15")
      (value "22")
      (footprint "0603R")
      (description "Resistor - 5%")
      (libsource (lib "贴片电阻电容") (part "Resistor - 5%"))
    )
    (comp (ref "R16")
      (value "22")
      (footprint "0603R")
      (description "Resistor - 5%")
      (libsource (lib "贴片电阻电容") (part "Resistor - 5%"))
    )
    (comp (ref "R17")
      (value "22")
      (footprint "0603R")
      (description "Resistor - 5%")
      (libsource (lib "贴片电阻电容") (part "Resistor - 5%"))
    )
    (comp (ref "R18")
      (value "22")
      (footprint "0603R")
      (description "Resistor - 5%")
      (libsource (lib "贴片电阻电容") (part "Resistor - 5%"))
    )
    (comp (ref "R19")
      (value "10K_5%")
      (footprint "0603R")
      (description "Resistor - 5%")
      (libsource (lib "贴片电阻电容") (part "Resistor - 5%"))
    )
    (comp (ref "R20")
      (value "10K_5%")
      (footprint "0603R")
      (description "Resistor - 5%")
      (libsource (lib "贴片电阻电容") (part "Resistor - 5%"))
    )
    (comp (ref "R21")
      (value "2K_5%")
      (footprint "0603R")
      (description "Resistor - 5%")
      (libsource (lib "贴片电阻电容") (part "Resistor - 5%"))
    )
    (comp (ref "R22")
      (value "3.01K")
      (footprint "0603R")
      (description "Resistor - 1%")
      (libsource (lib "贴片电阻电容") (part "Resistor - 1%"))
    )
    (comp (ref "R23")
      (value "3.01K")
      (footprint "0603R")
      (description "Resistor - 1%")
      (libsource (lib "贴片电阻电容") (part "Resistor - 1%"))
    )
    (comp (ref "R24")
      (value "10K_5%")
      (footprint "0603R")
      (description "Resistor - 5%")
      (libsource (lib "贴片电阻电容") (part "Resistor - 5%"))
    )
    (comp (ref "R25")
      (value "22")
      (footprint "0603R")
      (description "Resistor - 1%")
      (libsource (lib "贴片电阻电容") (part "Resistor - 1%"))
    )
    (comp (ref "R26")
      (value "22")
      (footprint "0603R")
      (description "Resistor - 1%")
      (libsource (lib "贴片电阻电容") (part "Resistor - 1%"))
    )
    (comp (ref "R27")
      (value "20K")
      (footprint "0603R")
      (description "Resistor - 1%")
      (libsource (lib "贴片电阻电容") (part "Resistor - 1%"))
    )
    (comp (ref "R28")
      (value "20K")
      (footprint "0603R")
      (description "Resistor - 1%")
      (libsource (lib "贴片电阻电容") (part "Resistor - 1%"))
    )
    (comp (ref "R29")
      (value "100Ω")
      (footprint "1210")
      (description "Resistor - 1%")
      (libsource (lib "贴片电阻电容") (part "Resistor - 1%"))
    )
    (comp (ref "R30")
      (value "100Ω")
      (footprint "1210")
      (description "Resistor - 1%")
      (libsource (lib "贴片电阻电容") (part "Resistor - 1%"))
    )
    (comp (ref "R31")
      (value "100Ω")
      (footprint "1210")
      (description "Resistor - 1%")
      (libsource (lib "贴片电阻电容") (part "Resistor - 1%"))
    )
    (comp (ref "R32")
      (value "100Ω")
      (footprint "1210")
      (description "Resistor - 1%")
      (libsource (lib "贴片电阻电容") (part "Resistor - 1%"))
    )
    (comp (ref "R33")
      (value "2.61K")
      (footprint "0603R")
      (description "Resistor - 1%")
      (libsource (lib "贴片电阻电容") (part "Resistor - 1%"))
    )
    (comp (ref "R34")
      (value "2.61K")
      (footprint "0603R")
      (description "Resistor - 1%")
      (libsource (lib "贴片电阻电容") (part "Resistor - 1%"))
    )
    (comp (ref "R35")
      (value "22")
      (footprint "0603R")
      (description "Resistor - 5%")
      (libsource (lib "贴片电阻电容") (part "Resistor - 5%"))
    )
    (comp (ref "R36")
      (value "22")
      (footprint "0603R")
      (description "Resistor - 5%")
      (libsource (lib "贴片电阻电容") (part "Resistor - 5%"))
    )
    (comp (ref "R37")
      (value "22")
      (footprint "0603R")
      (description "Resistor - 5%")
      (libsource (lib "贴片电阻电容") (part "Resistor - 5%"))
    )
    (comp (ref "R38")
      (value "22")
      (footprint "0603R")
      (description "Resistor - 5%")
      (libsource (lib "贴片电阻电容") (part "Resistor - 5%"))
    )
    (comp (ref "R39")
      (value "10K_5%")
      (footprint "0603R")
      (description "Resistor - 5%")
      (libsource (lib "贴片电阻电容") (part "Resistor - 5%"))
    )
    (comp (ref "R40")
      (value "2K_5%")
      (footprint "0603R")
      (description "Resistor - 5%")
      (libsource (lib "贴片电阻电容") (part "Resistor - 5%"))
    )
    (comp (ref "R41")
      (value "10K_5%")
      (footprint "0603R")
      (description "Resistor - 5%")
      (libsource (lib "贴片电阻电容") (part "Resistor - 5%"))
    )
    (comp (ref "R42")
      (value "10K_5%")
      (footprint "0603R")
      (description "Resistor - 5%")
      (libsource (lib "贴片电阻电容") (part "Resistor - 5%"))
    )
    (comp (ref "R43")
      (value "3.01K")
      (footprint "0603R")
      (description "Resistor - 1%")
      (libsource (lib "贴片电阻电容") (part "Resistor - 1%"))
    )
    (comp (ref "R44")
      (value "3.01K")
      (footprint "0603R")
      (description "Resistor - 1%")
      (libsource (lib "贴片电阻电容") (part "Resistor - 1%"))
    )
    (comp (ref "R45")
      (value "2K_5%")
      (footprint "0603R")
      (description "Resistor - 5%")
      (libsource (lib "贴片电阻电容") (part "Resistor - 5%"))
    )
    (comp (ref "R46")
      (value "22")
      (footprint "0603R")
      (description "Resistor - 1%")
      (libsource (lib "贴片电阻电容") (part "Resistor - 1%"))
    )
    (comp (ref "R47")
      (value "22")
      (footprint "0603R")
      (description "Resistor - 1%")
      (libsource (lib "贴片电阻电容") (part "Resistor - 1%"))
    )
    (comp (ref "R48")
      (value "20K")
      (footprint "0603R")
      (description "Resistor - 1%")
      (libsource (lib "贴片电阻电容") (part "Resistor - 1%"))
    )
    (comp (ref "R49")
      (value "20K")
      (footprint "0603R")
      (description "Resistor - 1%")
      (libsource (lib "贴片电阻电容") (part "Resistor - 1%"))
    )
    (comp (ref "R50")
      (value "100Ω")
      (footprint "1210")
      (description "Resistor - 1%")
      (libsource (lib "贴片电阻电容") (part "Resistor - 1%"))
    )
    (comp (ref "R51")
      (value "100Ω")
      (footprint "1210")
      (description "Resistor - 1%")
      (libsource (lib "贴片电阻电容") (part "Resistor - 1%"))
    )
    (comp (ref "R52")
      (value "100Ω")
      (footprint "1210")
      (description "Resistor - 1%")
      (libsource (lib "贴片电阻电容") (part "Resistor - 1%"))
    )
    (comp (ref "R53")
      (value "100Ω")
      (footprint "1210")
      (description "Resistor - 1%")
      (libsource (lib "贴片电阻电容") (part "Resistor - 1%"))
    )
    (comp (ref "R54")
      (value "2.61K")
      (footprint "0603R")
      (description "Resistor - 1%")
      (libsource (lib "贴片电阻电容") (part "Resistor - 1%"))
    )
    (comp (ref "R55")
      (value "2.61K")
      (footprint "0603R")
      (description "Resistor - 1%")
      (libsource (lib "贴片电阻电容") (part "Resistor - 1%"))
    )
    (comp (ref "R56")
      (value "10K_5%")
      (footprint "0603R")
      (description "Resistor - 5%")
      (libsource (lib "贴片电阻电容") (part "Resistor - 5%"))
    )
    (comp (ref "R57")
      (value "22")
      (footprint "0603R")
      (description "Resistor - 5%")
      (libsource (lib "贴片电阻电容") (part "Resistor - 5%"))
    )
    (comp (ref "R58")
      (value "22")
      (footprint "0603R")
      (description "Resistor - 5%")
      (libsource (lib "贴片电阻电容") (part "Resistor - 5%"))
    )
    (comp (ref "R59")
      (value "22")
      (footprint "0603R")
      (description "Resistor - 5%")
      (libsource (lib "贴片电阻电容") (part "Resistor - 5%"))
    )
    (comp (ref "R60")
      (value "22")
      (footprint "0603R")
      (description "Resistor - 5%")
      (libsource (lib "贴片电阻电容") (part "Resistor - 5%"))
    )
    (comp (ref "R61")
      (value "10K_5%")
      (footprint "0603R")
      (description "Resistor - 5%")
      (libsource (lib "贴片电阻电容") (part "Resistor - 5%"))
    )
    (comp (ref "R62")
      (value "2K_5%")
      (footprint "0603R")
      (description "Resistor - 5%")
      (libsource (lib "贴片电阻电容") (part "Resistor - 5%"))
    )
    (comp (ref "R63")
      (value "10K_5%")
      (footprint "0603R")
      (description "Resistor - 5%")
      (libsource (lib "贴片电阻电容") (part "Resistor - 5%"))
    )
    (comp (ref "R64")
      (value "3.01K")
      (footprint "0603R")
      (description "Resistor - 1%")
      (libsource (lib "贴片电阻电容") (part "Resistor - 1%"))
    )
    (comp (ref "R65")
      (value "22")
      (footprint "0603R")
      (description "Resistor - 1%")
      (libsource (lib "贴片电阻电容") (part "Resistor - 1%"))
    )
    (comp (ref "R66")
      (value "20K")
      (footprint "0603R")
      (description "Resistor - 1%")
      (libsource (lib "贴片电阻电容") (part "Resistor - 1%"))
    )
    (comp (ref "R67")
      (value "10K_5%")
      (footprint "0603R")
      (description "Resistor - 5%")
      (libsource (lib "贴片电阻电容") (part "Resistor - 5%"))
    )
    (comp (ref "R68")
      (value "100Ω")
      (footprint "1210")
      (description "Resistor - 1%")
      (libsource (lib "贴片电阻电容") (part "Resistor - 1%"))
    )
    (comp (ref "R69")
      (value "100Ω")
      (footprint "1210")
      (description "Resistor - 1%")
      (libsource (lib "贴片电阻电容") (part "Resistor - 1%"))
    )
    (comp (ref "R70")
      (value "2.61K")
      (footprint "0603R")
      (description "Resistor - 1%")
      (libsource (lib "贴片电阻电容") (part "Resistor - 1%"))
    )
    (comp (ref "R71")
      (value "2K_5%")
      (footprint "0603R")
      (description "Resistor - 5%")
      (libsource (lib "贴片电阻电容") (part "Resistor - 5%"))
    )
    (comp (ref "R72")
      (value "22")
      (footprint "0603R")
      (description "Resistor - 5%")
      (libsource (lib "贴片电阻电容") (part "Resistor - 5%"))
    )
    (comp (ref "R73")
      (value "22")
      (footprint "0603R")
      (description "Resistor - 5%")
      (libsource (lib "贴片电阻电容") (part "Resistor - 5%"))
    )
    (comp (ref "R74")
      (value "10K_5%")
      (footprint "0603R")
      (description "Resistor - 5%")
      (libsource (lib "贴片电阻电容") (part "Resistor - 5%"))
    )
    (comp (ref "R75")
      (value "10K_5%")
      (footprint "0603R")
      (description "Resistor - 5%")
      (libsource (lib "贴片电阻电容") (part "Resistor - 5%"))
    )
    (comp (ref "R76")
      (value "2K_5%")
      (footprint "0603R")
      (description "Resistor - 5%")
      (libsource (lib "贴片电阻电容") (part "Resistor - 5%"))
    )
    (comp (ref "R77")
      (value "3.01K")
      (footprint "0603R")
      (description "Resistor - 1%")
      (libsource (lib "贴片电阻电容") (part "Resistor - 1%"))
    )
    (comp (ref "R78")
      (value "10K_5%")
      (footprint "0603R")
      (description "Resistor - 5%")
      (libsource (lib "贴片电阻电容") (part "Resistor - 5%"))
    )
    (comp (ref "R79")
      (value "22")
      (footprint "0603R")
      (description "Resistor - 1%")
      (libsource (lib "贴片电阻电容") (part "Resistor - 1%"))
    )
    (comp (ref "R80")
      (value "20K")
      (footprint "0603R")
      (description "Resistor - 1%")
      (libsource (lib "贴片电阻电容") (part "Resistor - 1%"))
    )
    (comp (ref "R81")
      (value "100Ω")
      (footprint "1210")
      (description "Resistor - 1%")
      (libsource (lib "贴片电阻电容") (part "Resistor - 1%"))
    )
    (comp (ref "R82")
      (value "100Ω")
      (footprint "1210")
      (description "Resistor - 1%")
      (libsource (lib "贴片电阻电容") (part "Resistor - 1%"))
    )
    (comp (ref "R83")
      (value "2.61K")
      (footprint "0603R")
      (description "Resistor - 1%")
      (libsource (lib "贴片电阻电容") (part "Resistor - 1%"))
    )
    (comp (ref "R84")
      (value "22")
      (footprint "0603R")
      (description "Resistor - 5%")
      (libsource (lib "贴片电阻电容") (part "Resistor - 5%"))
    )
    (comp (ref "R85")
      (value "22")
      (footprint "0603R")
      (description "Resistor - 5%")
      (libsource (lib "贴片电阻电容") (part "Resistor - 5%"))
    )
    (comp (ref "R86")
      (value "10K_5%")
      (footprint "0603R")
      (description "Resistor - 5%")
      (libsource (lib "贴片电阻电容") (part "Resistor - 5%"))
    )
    (comp (ref "R87")
      (value "13K_1%")
      (footprint "0603R")
      (description "Resistor - 1%")
      (libsource (lib "贴片电阻电容") (part "Resistor - 1%"))
    )
    (comp (ref "R88")
      (value "2K_5%")
      (footprint "0603R")
      (description "Resistor - 5%")
      (libsource (lib "贴片电阻电容") (part "Resistor - 5%"))
    )
    (comp (ref "R89")
      (value "10K_1%")
      (footprint "0603R")
      (description "Resistor - 1%")
      (libsource (lib "贴片电阻电容") (part "Resistor - 1%"))
    )
    (comp (ref "R90")
      (value "10K_5%")
      (footprint "0603R")
      (description "Resistor - 5%")
      (libsource (lib "贴片电阻电容") (part "Resistor - 5%"))
    )
    (comp (ref "U7")
      (value "AD8027AR-SOIC8")
      (footprint "SO-8N")
      (libsource (lib "运放_集成电路") (part "AD8027AR-SOIC8"))
    )
    (comp (ref "U8")
      (value "AD8027AR-SOIC8")
      (footprint "SO-8N")
      (libsource (lib "运放_集成电路") (part "AD8027AR-SOIC8"))
    )
    (comp (ref "U9")
      (value "AD7276BUJZ")
      (footprint "SOT-23-6")
      (libsource (lib "运放_集成电路") (part "AD7276BUJZ"))
    )
    (comp (ref "U10")
      (value "AD7276BUJZ")
      (footprint "SOT-23-6")
      (libsource (lib "运放_集成电路") (part "AD7276BUJZ"))
    )
    (comp (ref "U11") (value "REF193GSZ") (footprint "SO-8N") (libsource (lib "运放_集成电路") (part "REF193GSZ")))
    (comp (ref "U12") (value "REF193GSZ") (footprint "SO-8N") (libsource (lib "运放_集成电路") (part "REF193GSZ")))
    (comp (ref "U13")
      (value "AD8027AR-SOIC8")
      (footprint "SO-8N")
      (libsource (lib "运放_集成电路") (part "AD8027AR-SOIC8"))
    )
    (comp (ref "U14")
      (value "AD8027AR-SOIC8")
      (footprint "SO-8N")
      (libsource (lib "运放_集成电路") (part "AD8027AR-SOIC8"))
    )
    (comp (ref "U15")
      (value "AD7276BUJZ")
      (footprint "SOT-23-6")
      (libsource (lib "运放_集成电路") (part "AD7276BUJZ"))
    )
    (comp (ref "U16")
      (value "AD7276BUJZ")
      (footprint "SOT-23-6")
      (libsource (lib "运放_集成电路") (part "AD7276BUJZ"))
    )
    (comp (ref "U17") (value "REF193GSZ") (footprint "SO-8N") (libsource (lib "运放_集成电路") (part "REF193GSZ")))
    (comp (ref "U18") (value "REF193GSZ") (footprint "SO-8N") (libsource (lib "运放_集成电路") (part "REF193GSZ")))
    (comp (ref "U19")
      (value "AD8027AR-SOIC8")
      (footprint "SO-8N")
      (libsource (lib "运放_集成电路") (part "AD8027AR-SOIC8"))
    )
    (comp (ref "U20")
      (value "AD8027AR-SOIC8")
      (footprint "SO-8N")
      (libsource (lib "运放_集成电路") (part "AD8027AR-SOIC8"))
    )
    (comp (ref "U21")
      (value "AD7276BUJZ")
      (footprint "SOT-23-6")
      (libsource (lib "运放_集成电路") (part "AD7276BUJZ"))
    )
    (comp (ref "U22")
      (value "AD7276BUJZ")
      (footprint "SOT-23-6")
      (libsource (lib "运放_集成电路") (part "AD7276BUJZ"))
    )
    (comp (ref "U23") (value "REF193GSZ") (footprint "SO-8N") (libsource (lib "运放_集成电路") (part "REF193GSZ")))
    (comp (ref "U24") (value "REF193GSZ") (footprint "SO-8N") (libsource (lib "运放_集成电路") (part "REF193GSZ")))
    (comp (ref "U25")
      (value "AD8027AR-SOIC8")
      (footprint "SO-8N")
      (libsource (lib "运放_集成电路") (part "AD8027AR-SOIC8"))
    )
    (comp (ref "U26")
      (value "AD7276BUJZ")
      (footprint "SOT-23-6")
      (libsource (lib "运放_集成电路") (part "AD7276BUJZ"))
    )
    (comp (ref "U27") (value "REF193GSZ") (footprint "SO-8N") (libsource (lib "运放_集成电路") (part "REF193GSZ")))
    (comp (ref "U28")
      (value "AD8027AR-SOIC8")
      (footprint "SO-8N")
      (libsource (lib "运放_集成电路") (part "AD8027AR-SOIC8"))
    )
    (comp (ref "U29")
      (value "OP284ES")
      (footprint "SO-8_N")
      (description "Precision Rail-to-Rail Input and Output Operational Amplifier")
      (fields (field (name "PUBLISHER") "Altium Limited"))
      (libsource (lib "AD Operational Amplifier") (part "OP284ES"))
    )
    (comp (ref "U30")
      (value "AD7276BUJZ")
      (footprint "SOT-23-6")
      (libsource (lib "运放_集成电路") (part "AD7276BUJZ"))
    )
    (comp (ref "U31") (value "REF193GSZ") (footprint "SO-8N") (libsource (lib "") (part "REF193GSZ_1")))
    (comp (ref "U32") (value "REF193GSZ") (footprint "SO-8N") (libsource (lib "运放_集成电路") (part "REF193GSZ")))
  )
  (nets
    (net (code "1") (name "/AD7276_CS1") (class "Default")
      (node (ref "U9") (pin "6") (pinfunction "~{CS}_6") (pintype "passive"))
    )
    (net (code "2") (name "/AD7276_CS2") (class "Default")
      (node (ref "U15") (pin "6") (pinfunction "~{CS}_6") (pintype "passive"))
    )
    (net (code "3") (name "/AD7276_CS3") (class "Default")
      (node (ref "U21") (pin "6") (pinfunction "~{CS}_6") (pintype "passive"))
    )
    (net (code "4") (name "/AD7276_CS4") (class "Default")
      (node (ref "U26") (pin "6") (pinfunction "~{CS}_6") (pintype "passive"))
    )
    (net (code "5") (name "/AD7276_CS5") (class "Default")
      (node (ref "U30") (pin "6") (pinfunction "~{CS}_6") (pintype "passive"))
    )
    (net (code "6") (name "/AD7276_CS6") (class "Default")
      (node (ref "U10") (pin "6") (pinfunction "~{CS}_6") (pintype "passive"))
    )
    (net (code "7") (name "/AD7276_CS7") (class "Default")
      (node (ref "U16") (pin "6") (pinfunction "~{CS}_6") (pintype "passive"))
    )
    (net (code "8") (name "/AD7276_CS8") (class "Default")
      (node (ref "U22") (pin "6") (pinfunction "~{CS}_6") (pintype "passive"))
    )
    (net (code "9") (name "/AD7276_SCLK1") (class "Default")
      (node (ref "U9") (pin "4") (pinfunction "SCLK_4") (pintype "passive"))
    )
    (net (code "10") (name "/AD7276_SCLK2") (class "Default")
      (node (ref "U15") (pin "4") (pinfunction "SCLK_4") (pintype "passive"))
    )
    (net (code "11") (name "/AD7276_SCLK3") (class "Default")
      (node (ref "U21") (pin "4") (pinfunction "SCLK_4") (pintype "passive"))
    )
    (net (code "12") (name "/AD7276_SCLK4") (class "Default")
      (node (ref "U26") (pin "4") (pinfunction "SCLK_4") (pintype "passive"))
    )
    (net (code "13") (name "/AD7276_SCLK5") (class "Default")
      (node (ref "U30") (pin "4") (pinfunction "SCLK_4") (pintype "passive"))
    )
    (net (code "14") (name "/AD7276_SCLK6") (class "Default")
      (node (ref "U10") (pin "4") (pinfunction "SCLK_4") (pintype "passive"))
    )
    (net (code "15") (name "/AD7276_SCLK7") (class "Default")
      (node (ref "U16") (pin "4") (pinfunction "SCLK_4") (pintype "passive"))
    )
    (net (code "16") (name "/AD7276_SCLK8") (class "Default")
      (node (ref "U22") (pin "4") (pinfunction "SCLK_4") (pintype "passive"))
    )
    (net (code "17") (name "/AD7276_SDATA1") (class "Default")
      (node (ref "U9") (pin "5") (pinfunction "SDATA_5") (pintype "passive"))
    )
    (net (code "18") (name "/AD7276_SDATA2") (class "Default")
      (node (ref "U15") (pin "5") (pinfunction "SDATA_5") (pintype "passive"))
    )
    (net (code "19") (name "/AD7276_SDATA3") (class "Default")
      (node (ref "U21") (pin "5") (pinfunction "SDATA_5") (pintype "passive"))
    )
    (net (code "20") (name "/AD7276_SDATA4") (class "Default")
      (node (ref "U26") (pin "5") (pinfunction "SDATA_5") (pintype "passive"))
    )
    (net (code "21") (name "/AD7276_SDATA5") (class "Default")
      (node (ref "U30") (pin "5") (pinfunction "SDATA_5") (pintype "passive"))
    )
    (net (code "22") (name "/AD7276_SDATA6") (class "Default")
      (node (ref "U10") (pin "5") (pinfunction "SDATA_5") (pintype "passive"))
    )
    (net (code "23") (name "/AD7276_SDATA7") (class "Default")
      (node (ref "U16") (pin "5") (pinfunction "SDATA_5") (pintype "passive"))
    )
    (net (code "24") (name "/AD7276_SDATA8") (class "Default")
      (node (ref "U22") (pin "5") (pinfunction "SDATA_5") (pintype "passive"))
    )
    (net (code "25") (name "/AST1") (class "Default")
      (node (ref "P2") (pin "1") (pinfunction "1_1") (pintype "passive"))
      (node (ref "Q1") (pin "3") (pinfunction "C_3") (pintype "passive"))
      (node (ref "R19") (pin "2") (pinfunction "2_2") (pintype "passive"))
    )
    (net (code "26") (name "/AST2") (class "Default")
      (node (ref "P2") (pin "2") (pinfunction "2_2") (pintype "passive"))
      (node (ref "Q2") (pin "3") (pinfunction "C_3") (pintype "passive"))
      (node (ref "R24") (pin "2") (pinfunction "2_2") (pintype "passive"))
    )
    (net (code "27") (name "/AST3") (class "Default")
      (node (ref "P2") (pin "3") (pinfunction "3_3") (pintype "passive"))
      (node (ref "Q3") (pin "3") (pinfunction "C_3") (pintype "passive"))
      (node (ref "R41") (pin "2") (pinfunction "2_2") (pintype "passive"))
    )
    (net (code "28") (name "/AST4") (class "Default")
      (node (ref "P2") (pin "4") (pinfunction "4_4") (pintype "passive"))
      (node (ref "Q4") (pin "3") (pinfunction "C_3") (pintype "passive"))
      (node (ref "R56") (pin "2") (pinfunction "2_2") (pintype "passive"))
    )
    (net (code "29") (name "/AST5") (class "Default")
      (node (ref "P2") (pin "5") (pinfunction "5_5") (pintype "passive"))
      (node (ref "Q5") (pin "3") (pinfunction "C_3") (pintype "passive"))
      (node (ref "R63") (pin "2") (pinfunction "2_2") (pintype "passive"))
    )
    (net (code "30") (name "/AST6") (class "Default")
      (node (ref "P2") (pin "6") (pinfunction "6_6") (pintype "passive"))
      (node (ref "Q6") (pin "3") (pinfunction "C_3") (pintype "passive"))
      (node (ref "R74") (pin "2") (pinfunction "2_2") (pintype "passive"))
    )
    (net (code "31") (name "/AST7") (class "Default")
      (node (ref "P2") (pin "7") (pinfunction "7_7") (pintype "passive"))
      (node (ref "Q7") (pin "3") (pinfunction "C_3") (pintype "passive"))
      (node (ref "R78") (pin "2") (pinfunction "2_2") (pintype "passive"))
    )
    (net (code "32") (name "/AST8") (class "Default")
      (node (ref "P2") (pin "8") (pinfunction "8_8") (pintype "passive"))
      (node (ref "Q8") (pin "3") (pinfunction "C_3") (pintype "passive"))
      (node (ref "R90") (pin "2") (pinfunction "2_2") (pintype "passive"))
    )
    (net (code "33") (name "/AST_Ctrl1") (class "Default")
      (node (ref "R14") (pin "1") (pinfunction "1_1") (pintype "passive"))
    )
    (net (code "34") (name "/AST_Ctrl2") (class "Default")
      (node (ref "R21") (pin "1") (pinfunction "1_1") (pintype "passive"))
    )
    (net (code "35") (name "/AST_Ctrl3") (class "Default")
      (node (ref "R40") (pin "1") (pinfunction "1_1") (pintype "passive"))
    )
    (net (code "36") (name "/AST_Ctrl4") (class "Default")
      (node (ref "R45") (pin "1") (pinfunction "1_1") (pintype "passive"))
    )
    (net (code "37") (name "/AST_Ctrl5") (class "Default")
      (node (ref "R62") (pin "1") (pinfunction "1_1") (pintype "passive"))
    )
    (net (code "38") (name "/AST_Ctrl6") (class "Default")
      (node (ref "R71") (pin "1") (pinfunction "1_1") (pintype "passive"))
    )
    (net (code "39") (name "/AST_Ctrl7") (class "Default")
      (node (ref "R76") (pin "1") (pinfunction "1_1") (pintype "passive"))
    )
    (net (code "40") (name "/AST_Ctrl8") (class "Default")
      (node (ref "R88") (pin "1") (pinfunction "1_1") (pintype "passive"))
    )
    (net (code "41") (name "/Signal1") (class "Default")
      (node (ref "C26") (pin "1") (pinfunction "1_1") (pintype "passive"))
      (node (ref "P1") (pin "1") (pinfunction "1_1") (pintype "passive"))
      (node (ref "R7") (pin "2") (pinfunction "2_2") (pintype "passive"))
      (node (ref "R8") (pin "2") (pinfunction "2_2") (pintype "passive"))
    )
    (net (code "42") (name "/Signal2") (class "Default")
      (node (ref "C57") (pin "1") (pinfunction "1_1") (pintype "passive"))
      (node (ref "P1") (pin "2") (pinfunction "2_2") (pintype "passive"))
      (node (ref "R29") (pin "2") (pinfunction "2_2") (pintype "passive"))
      (node (ref "R30") (pin "2") (pinfunction "2_2") (pintype "passive"))
    )
    (net (code "43") (name "/Signal3") (class "Default")
      (node (ref "C89") (pin "1") (pinfunction "1_1") (pintype "passive"))
      (node (ref "P1") (pin "3") (pinfunction "3_3") (pintype "passive"))
      (node (ref "R50") (pin "2") (pinfunction "2_2") (pintype "passive"))
      (node (ref "R51") (pin "2") (pinfunction "2_2") (pintype "passive"))
    )
    (net (code "44") (name "/Signal4") (class "Default")
      (node (ref "C120") (pin "1") (pinfunction "1_1") (pintype "passive"))
      (node (ref "P1") (pin "4") (pinfunction "4_4") (pintype "passive"))
      (node (ref "R68") (pin "2") (pinfunction "2_2") (pintype "passive"))
      (node (ref "R69") (pin "2") (pinfunction "2_2") (pintype "passive"))
    )
    (net (code "45") (name "/Signal5") (class "Default")
      (node (ref "C136") (pin "1") (pinfunction "1_1") (pintype "passive"))
      (node (ref "P1") (pin "5") (pinfunction "5_5") (pintype "passive"))
      (node (ref "R81") (pin "2") (pinfunction "2_2") (pintype "passive"))
      (node (ref "R82") (pin "2") (pinfunction "2_2") (pintype "passive"))
    )
    (net (code "46") (name "/Signal6") (class "Default")
      (node (ref "C27") (pin "1") (pinfunction "1_1") (pintype "passive"))
      (node (ref "P1") (pin "6") (pinfunction "6_6") (pintype "passive"))
      (node (ref "R10") (pin "2") (pinfunction "2_2") (pintype "passive"))
      (node (ref "R9") (pin "2") (pinfunction "2_2") (pintype "passive"))
    )
    (net (code "47") (name "/Signal7") (class "Default")
      (node (ref "C58") (pin "1") (pinfunction "1_1") (pintype "passive"))
      (node (ref "P1") (pin "7") (pinfunction "7_7") (pintype "passive"))
      (node (ref "R31") (pin "2") (pinfunction "2_2") (pintype "passive"))
      (node (ref "R32") (pin "2") (pinfunction "2_2") (pintype "passive"))
    )
    (net (code "48") (name "/Signal8") (class "Default")
      (node (ref "C90") (pin "1") (pinfunction "1_1") (pintype "passive"))
      (node (ref "P1") (pin "8") (pinfunction "8_8") (pintype "passive"))
      (node (ref "R52") (pin "2") (pinfunction "2_2") (pintype "passive"))
      (node (ref "R53") (pin "2") (pinfunction "2_2") (pintype "passive"))
    )
    (net (code "49") (name "GND") (class "Default")
      (node (ref "C100") (pin "1") (pinfunction "1_1") (pintype "passive"))
      (node (ref "C101") (pin "1") (pinfunction "1_1") (pintype "passive"))
      (node (ref "C102") (pin "1") (pinfunction "1_1") (pintype "passive"))
      (node (ref "C103") (pin "1") (pinfunction "1_1") (pintype "passive"))
      (node (ref "C104") (pin "2") (pinfunction "2_2") (pintype "passive"))
      (node (ref "C105") (pin "1") (pinfunction "1_1") (pintype "passive"))
      (node (ref "C106") (pin "1") (pinfunction "1_1") (pintype "passive"))
      (node (ref "C107") (pin "1") (pinfunction "1_1") (pintype "passive"))
      (node (ref "C108") (pin "1") (pinfunction "1_1") (pintype "passive"))
      (node (ref "C109") (pin "1") (pinfunction "1_1") (pintype "passive"))
      (node (ref "C110") (pin "1") (pinfunction "1_1") (pintype "passive"))
      (node (ref "C111") (pin "1") (pinfunction "1_1") (pintype "passive"))
      (node (ref "C112") (pin "1") (pinfunction "1_1") (pintype "passive"))
      (node (ref "C113") (pin "1") (pinfunction "1_1") (pintype "passive"))
      (node (ref "C114") (pin "1") (pinfunction "1_1") (pintype "passive"))
      (node (ref "C115") (pin "1") (pinfunction "1_1") (pintype "passive"))
      (node (ref "C116") (pin "2") (pinfunction "2_2") (pintype "passive"))
      (node (ref "C117") (pin "2") (pinfunction "2_2") (pintype "passive"))
      (node (ref "C119") (pin "1") (pinfunction "1_1") (pintype "passive"))
      (node (ref "C121") (pin "1") (pinfunction "1_1") (pintype "passive"))
      (node (ref "C122") (pin "1") (pinfunction "1_1") (pintype "passive"))
      (node (ref "C123") (pin "1") (pinfunction "1_1") (pintype "passive"))
      (node (ref "C124") (pin "1") (pinfunction "1_1") (pintype "passive"))
      (node (ref "C125") (pin "1") (pinfunction "1_1") (pintype "passive"))
      (node (ref "C126") (pin "1") (pinfunction "1_1") (pintype "passive"))
      (node (ref "C127") (pin "1") (pinfunction "1_1") (pintype "passive"))
      (node (ref "C128") (pin "1") (pinfunction "1_1") (pintype "passive"))
      (node (ref "C129") (pin "1") (pinfunction "1_1") (pintype "passive"))
      (node (ref "C130") (pin "1") (pinfunction "1_1") (pintype "passive"))
      (node (ref "C131") (pin "1") (pinfunction "1_1") (pintype "passive"))
      (node (ref "C132") (pin "1") (pinfunction "1_1") (pintype "passive"))
      (node (ref "C133") (pin "2") (pinfunction "2_2") (pintype "passive"))
      (node (ref "C134") (pin "1") (pinfunction "1_1") (pintype "passive"))
      (node (ref "C137") (pin "1") (pinfunction "1_1") (pintype "passive"))
      (node (ref "C138") (pin "1") (pinfunction "1_1") (pintype "passive"))
      (node (ref "C139") (pin "1") (pinfunction "1_1") (pintype "passive"))
      (node (ref "C140") (pin "1") (pinfunction "1_1") (pintype "passive"))
      (node (ref "C141") (pin "1") (pinfunction "1_1") (pintype "passive"))
      (node (ref "C142") (pin "1") (pinfunction "1_1") (pintype "passive"))
      (node (ref "C143") (pin "1") (pinfunction "1_1") (pintype "passive"))
      (node (ref "C144") (pin "1") (pinfunction "1_1") (pintype "passive"))
      (node (ref "C145") (pin "1") (pinfunction "1_1") (pintype "passive"))
      (node (ref "C146") (pin "1") (pinfunction "1_1") (pintype "passive"))
      (node (ref "C147") (pin "1") (pinfunction "1_1") (pintype "passive"))
      (node (ref "C148") (pin "1") (pinfunction "1_1") (pintype "passive"))
      (node (ref "C149") (pin "2") (pinfunction "2_2") (pintype "passive"))
      (node (ref "C150") (pin "1") (pinfunction "1_1") (pintype "passive"))
      (node (ref "C151") (pin "1") (pinfunction "1_1") (pintype "passive"))
      (node (ref "C152") (pin "1") (pinfunction "1_1") (pintype "passive"))
      (node (ref "C153") (pin "1") (pinfunction "1_1") (pintype "passive"))
      (node (ref "C154") (pin "1") (pinfunction "1_1") (pintype "passive"))
      (node (ref "C155") (pin "1") (pinfunction "1_1") (pintype "passive"))
      (node (ref "C156") (pin "2") (pinfunction "2_2") (pintype "passive"))
      (node (ref "C25") (pin "1") (pinfunction "1_1") (pintype "passive"))
      (node (ref "C28") (pin "1") (pinfunction "1_1") (pintype "passive"))
      (node (ref "C29") (pin "1") (pinfunction "1_1") (pintype "passive"))
      (node (ref "C30") (pin "1") (pinfunction "1_1") (pintype "passive"))
      (node (ref "C31") (pin "1") (pinfunction "1_1") (pintype "passive"))
      (node (ref "C32") (pin "1") (pinfunction "1_1") (pintype "passive"))
      (node (ref "C33") (pin "1") (pinfunction "1_1") (pintype "passive"))
      (node (ref "C34") (pin "1") (pinfunction "1_1") (pintype "passive"))
      (node (ref "C35") (pin "1") (pinfunction "1_1") (pintype "passive"))
      (node (ref "C36") (pin "1") (pinfunction "1_1") (pintype "passive"))
      (node (ref "C37") (pin "1") (pinfunction "1_1") (pintype "passive"))
      (node (ref "C38") (pin "1") (pinfunction "1_1") (pintype "passive"))
      (node (ref "C39") (pin "1") (pinfunction "1_1") (pintype "passive"))
      (node (ref "C40") (pin "1") (pinfunction "1_1") (pintype "passive"))
      (node (ref "C41") (pin "1") (pinfunction "1_1") (pintype "passive"))
      (node (ref "C42") (pin "1") (pinfunction "1_1") (pintype "passive"))
      (node (ref "C43") (pin "1") (pinfunction "1_1") (pintype "passive"))
      (node (ref "C44") (pin "1") (pinfunction "1_1") (pintype "passive"))
      (node (ref "C45") (pin "1") (pinfunction "1_1") (pintype "passive"))
      (node (ref "C46") (pin "1") (pinfunction "1_1") (pintype "passive"))
      (node (ref "C47") (pin "1") (pinfunction "1_1") (pintype "passive"))
      (node (ref "C48") (pin "1") (pinfunction "1_1") (pintype "passive"))
      (node (ref "C49") (pin "1") (pinfunction "1_1") (pintype "passive"))
      (node (ref "C50") (pin "1") (pinfunction "1_1") (pintype "passive"))
      (node (ref "C51") (pin "1") (pinfunction "1_1") (pintype "passive"))
      (node (ref "C52") (pin "2") (pinfunction "2_2") (pintype "passive"))
      (node (ref "C53") (pin "2") (pinfunction "2_2") (pintype "passive"))
      (node (ref "C54") (pin "1") (pinfunction "1_1") (pintype "passive"))
      (node (ref "C59") (pin "1") (pinfunction "1_1") (pintype "passive"))
      (node (ref "C60") (pin "1") (pinfunction "1_1") (pintype "passive"))
      (node (ref "C61") (pin "1") (pinfunction "1_1") (pintype "passive"))
      (node (ref "C62") (pin "1") (pinfunction "1_1") (pintype "passive"))
      (node (ref "C63") (pin "1") (pinfunction "1_1") (pintype "passive"))
      (node (ref "C64") (pin "1") (pinfunction "1_1") (pintype "passive"))
      (node (ref "C65") (pin "1") (pinfunction "1_1") (pintype "passive"))
      (node (ref "C66") (pin "1") (pinfunction "1_1") (pintype "passive"))
      (node (ref "C67") (pin "1") (pinfunction "1_1") (pintype "passive"))
      (node (ref "C68") (pin "1") (pinfunction "1_1") (pintype "passive"))
      (node (ref "C69") (pin "1") (pinfunction "1_1") (pintype "passive"))
      (node (ref "C70") (pin "1") (pinfunction "1_1") (pintype "passive"))
      (node (ref "C71") (pin "1") (pinfunction "1_1") (pintype "passive"))
      (node (ref "C72") (pin "1") (pinfunction "1_1") (pintype "passive"))
      (node (ref "C73") (pin "1") (pinfunction "1_1") (pintype "passive"))
      (node (ref "C74") (pin "1") (pinfunction "1_1") (pintype "passive"))
      (node (ref "C75") (pin "1") (pinfunction "1_1") (pintype "passive"))
      (node (ref "C76") (pin "1") (pinfunction "1_1") (pintype "passive"))
      (node (ref "C77") (pin "1") (pinfunction "1_1") (pintype "passive"))
      (node (ref "C78") (pin "1") (pinfunction "1_1") (pintype "passive"))
      (node (ref "C79") (pin "1") (pinfunction "1_1") (pintype "passive"))
      (node (ref "C80") (pin "1") (pinfunction "1_1") (pintype "passive"))
      (node (ref "C81") (pin "1") (pinfunction "1_1") (pintype "passive"))
      (node (ref "C82") (pin "1") (pinfunction "1_1") (pintype "passive"))
      (node (ref "C83") (pin "1") (pinfunction "1_1") (pintype "passive"))
      (node (ref "C84") (pin "2") (pinfunction "2_2") (pintype "passive"))
      (node (ref "C85") (pin "2") (pinfunction "2_2") (pintype "passive"))
      (node (ref "C86") (pin "1") (pinfunction "1_1") (pintype "passive"))
      (node (ref "C91") (pin "1") (pinfunction "1_1") (pintype "passive"))
      (node (ref "C92") (pin "1") (pinfunction "1_1") (pintype "passive"))
      (node (ref "C93") (pin "1") (pinfunction "1_1") (pintype "passive"))
      (node (ref "C94") (pin "1") (pinfunction "1_1") (pintype "passive"))
      (node (ref "C95") (pin "1") (pinfunction "1_1") (pintype "passive"))
      (node (ref "C96") (pin "1") (pinfunction "1_1") (pintype "passive"))
      (node (ref "C97") (pin "1") (pinfunction "1_1") (pintype "passive"))
      (node (ref "C98") (pin "1") (pinfunction "1_1") (pintype "passive"))
      (node (ref "C99") (pin "1") (pinfunction "1_1") (pintype "passive"))
      (node (ref "P1") (pin "11") (pinfunction "11_11") (pintype "passive"))
      (node (ref "P1") (pin "12") (pinfunction "12_12") (pintype "passive"))
      (node (ref "P2") (pin "10") (pinfunction "10_10") (pintype "passive"))
      (node (ref "P2") (pin "9") (pinfunction "9_9") (pintype "passive"))
      (node (ref "R10") (pin "1") (pinfunction "1_1") (pintype "passive"))
      (node (ref "R19") (pin "1") (pinfunction "1_1") (pintype "passive"))
      (node (ref "R24") (pin "1") (pinfunction "1_1") (pintype "passive"))
      (node (ref "R29") (pin "1") (pinfunction "1_1") (pintype "passive"))
      (node (ref "R30") (pin "1") (pinfunction "1_1") (pintype "passive"))
      (node (ref "R31") (pin "1") (pinfunction "1_1") (pintype "passive"))
      (node (ref "R32") (pin "1") (pinfunction "1_1") (pintype "passive"))
      (node (ref "R41") (pin "1") (pinfunction "1_1") (pintype "passive"))
      (node (ref "R50") (pin "1") (pinfunction "1_1") (pintype "passive"))
      (node (ref "R51") (pin "1") (pinfunction "1_1") (pintype "passive"))
      (node (ref "R52") (pin "1") (pinfunction "1_1") (pintype "passive"))
      (node (ref "R53") (pin "1") (pinfunction "1_1") (pintype "passive"))
      (node (ref "R56") (pin "1") (pinfunction "1_1") (pintype "passive"))
      (node (ref "R63") (pin "1") (pinfunction "1_1") (pintype "passive"))
      (node (ref "R68") (pin "1") (pinfunction "1_1") (pintype "passive"))
      (node (ref "R69") (pin "1") (pinfunction "1_1") (pintype "passive"))
      (node (ref "R7") (pin "1") (pinfunction "1_1") (pintype "passive"))
      (node (ref "R74") (pin "1") (pinfunction "1_1") (pintype "passive"))
      (node (ref "R78") (pin "1") (pinfunction "1_1") (pintype "passive"))
      (node (ref "R8") (pin "1") (pinfunction "1_1") (pintype "passive"))
      (node (ref "R81") (pin "1") (pinfunction "1_1") (pintype "passive"))
      (node (ref "R82") (pin "1") (pinfunction "1_1") (pintype "passive"))
      (node (ref "R89") (pin "1") (pinfunction "1_1") (pintype "passive"))
      (node (ref "R9") (pin "1") (pinfunction "1_1") (pintype "passive"))
      (node (ref "R90") (pin "1") (pinfunction "1_1") (pintype "passive"))
      (node (ref "U10") (pin "2") (pinfunction "GND_2") (pintype "passive"))
      (node (ref "U11") (pin "4") (pinfunction "GND_4") (pintype "passive"))
      (node (ref "U12") (pin "4") (pinfunction "GND_4") (pintype "passive"))
      (node (ref "U15") (pin "2") (pinfunction "GND_2") (pintype "passive"))
      (node (ref "U16") (pin "2") (pinfunction "GND_2") (pintype "passive"))
      (node (ref "U17") (pin "4") (pinfunction "GND_4") (pintype "passive"))
      (node (ref "U18") (pin "4") (pinfunction "GND_4") (pintype "passive"))
      (node (ref "U21") (pin "2") (pinfunction "GND_2") (pintype "passive"))
      (node (ref "U22") (pin "2") (pinfunction "GND_2") (pintype "passive"))
      (node (ref "U23") (pin "4") (pinfunction "GND_4") (pintype "passive"))
      (node (ref "U24") (pin "4") (pinfunction "GND_4") (pintype "passive"))
      (node (ref "U26") (pin "2") (pinfunction "GND_2") (pintype "passive"))
      (node (ref "U27") (pin "4") (pinfunction "GND_4") (pintype "passive"))
      (node (ref "U29") (pin "4") (pinfunction "V-_4") (pintype "power_in"))
      (node (ref "U30") (pin "2") (pinfunction "GND_2") (pintype "passive"))
      (node (ref "U31") (pin "4") (pinfunction "GND_4") (pintype "passive"))
      (node (ref "U32") (pin "4") (pinfunction "GND_4") (pintype "passive"))
      (node (ref "U9") (pin "2") (pinfunction "GND_2") (pintype "passive"))
    )
    (net (code "50") (name "Net-(C26-Pad2)") (class "Default")
      (node (ref "C26") (pin "2") (pinfunction "2_2") (pintype "passive"))
      (node (ref "R5") (pin "1") (pinfunction "1_1") (pintype "passive"))
    )
    (net (code "51") (name "Net-(C27-Pad2)") (class "Default")
      (node (ref "C27") (pin "2") (pinfunction "2_2") (pintype "passive"))
      (node (ref "R6") (pin "1") (pinfunction "1_1") (pintype "passive"))
    )
    (net (code "52") (name "Net-(C57-Pad2)") (class "Default")
      (node (ref "C57") (pin "2") (pinfunction "2_2") (pintype "passive"))
      (node (ref "R27") (pin "1") (pinfunction "1_1") (pintype "passive"))
    )
    (net (code "53") (name "Net-(C58-Pad2)") (class "Default")
      (node (ref "C58") (pin "2") (pinfunction "2_2") (pintype "passive"))
      (node (ref "R28") (pin "1") (pinfunction "1_1") (pintype "passive"))
    )
    (net (code "54") (name "Net-(C89-Pad2)") (class "Default")
      (node (ref "C89") (pin "2") (pinfunction "2_2") (pintype "passive"))
      (node (ref "R48") (pin "1") (pinfunction "1_1") (pintype "passive"))
    )
    (net (code "55") (name "Net-(C90-Pad2)") (class "Default")
      (node (ref "C90") (pin "2") (pinfunction "2_2") (pintype "passive"))
      (node (ref "R49") (pin "1") (pinfunction "1_1") (pintype "passive"))
    )
    (net (code "56") (name "Net-(C120-Pad2)") (class "Default")
      (node (ref "C120") (pin "2") (pinfunction "2_2") (pintype "passive"))
      (node (ref "R66") (pin "1") (pinfunction "1_1") (pintype "passive"))
    )
    (net (code "57") (name "Net-(C136-Pad2)") (class "Default")
      (node (ref "C136") (pin "2") (pinfunction "2_2") (pintype "passive"))
      (node (ref "R80") (pin "1") (pinfunction "1_1") (pintype "passive"))
    )
    (net (code "58") (name "Net-(Q1-B)") (class "Default")
      (node (ref "Q1") (pin "1") (pinfunction "B_1") (pintype "passive"))
      (node (ref "R11") (pin "1") (pinfunction "1_1") (pintype "passive"))
      (node (ref "R14") (pin "2") (pinfunction "2_2") (pintype "passive"))
    )
    (net (code "59") (name "Net-(Q2-B)") (class "Default")
      (node (ref "Q2") (pin "1") (pinfunction "B_1") (pintype "passive"))
      (node (ref "R20") (pin "1") (pinfunction "1_1") (pintype "passive"))
      (node (ref "R21") (pin "2") (pinfunction "2_2") (pintype "passive"))
    )
    (net (code "60") (name "Net-(Q3-B)") (class "Default")
      (node (ref "Q3") (pin "1") (pinfunction "B_1") (pintype "passive"))
      (node (ref "R39") (pin "1") (pinfunction "1_1") (pintype "passive"))
      (node (ref "R40") (pin "2") (pinfunction "2_2") (pintype "passive"))
    )
    (net (code "61") (name "Net-(Q4-B)") (class "Default")
      (node (ref "Q4") (pin "1") (pinfunction "B_1") (pintype "passive"))
      (node (ref "R42") (pin "1") (pinfunction "1_1") (pintype "passive"))
      (node (ref "R45") (pin "2") (pinfunction "2_2") (pintype "passive"))
    )
    (net (code "62") (name "Net-(Q5-B)") (class "Default")
      (node (ref "Q5") (pin "1") (pinfunction "B_1") (pintype "passive"))
      (node (ref "R61") (pin "1") (pinfunction "1_1") (pintype "passive"))
      (node (ref "R62") (pin "2") (pinfunction "2_2") (pintype "passive"))
    )
    (net (code "63") (name "Net-(Q6-B)") (class "Default")
      (node (ref "Q6") (pin "1") (pinfunction "B_1") (pintype "passive"))
      (node (ref "R67") (pin "1") (pinfunction "1_1") (pintype "passive"))
      (node (ref "R71") (pin "2") (pinfunction "2_2") (pintype "passive"))
    )
    (net (code "64") (name "Net-(Q7-B)") (class "Default")
      (node (ref "Q7") (pin "1") (pinfunction "B_1") (pintype "passive"))
      (node (ref "R75") (pin "1") (pinfunction "1_1") (pintype "passive"))
      (node (ref "R76") (pin "2") (pinfunction "2_2") (pintype "passive"))
    )
    (net (code "65") (name "Net-(Q8-B)") (class "Default")
      (node (ref "Q8") (pin "1") (pinfunction "B_1") (pintype "passive"))
      (node (ref "R86") (pin "1") (pinfunction "1_1") (pintype "passive"))
      (node (ref "R88") (pin "2") (pinfunction "2_2") (pintype "passive"))
    )
    (net (code "66") (name "Net-(U7-+IN)") (class "Default")
      (node (ref "R12") (pin "2") (pinfunction "2_2") (pintype "passive"))
      (node (ref "U7") (pin "3") (pinfunction "+IN_3") (pintype "passive"))
    )
    (net (code "67") (name "Net-(U7-+Vs)") (class "Default")
      (node (ref "C34") (pin "2") (pinfunction "2_2") (pintype "passive"))
      (node (ref "C35") (pin "2") (pinfunction "2_2") (pintype "passive"))
      (node (ref "R16") (pin "1") (pinfunction "1_1") (pintype "passive"))
      (node (ref "U7") (pin "7") (pinfunction "+Vs_7") (pintype "passive"))
    )
    (net (code "68") (name "Net-(U7--IN)") (class "Default")
      (node (ref "C23") (pin "2") (pinfunction "2_2") (pintype "passive"))
      (node (ref "R1") (pin "1") (pinfunction "1_1") (pintype "passive"))
      (node (ref "R5") (pin "2") (pinfunction "2_2") (pintype "passive"))
      (node (ref "U7") (pin "2") (pinfunction "-IN_2") (pintype "passive"))
    )
    (net (code "69") (name "Net-(U7--Vs)") (class "Default")
      (node (ref "C32") (pin "2") (pinfunction "2_2") (pintype "passive"))
      (node (ref "C33") (pin "2") (pinfunction "2_2") (pintype "passive"))
      (node (ref "R15") (pin "2") (pinfunction "2_2") (pintype "passive"))
      (node (ref "U7") (pin "4") (pinfunction "-Vs_4") (pintype "passive"))
    )
    (net (code "70") (name "Net-(U7-VOUT)") (class "Default")
      (node (ref "C23") (pin "1") (pinfunction "1_1") (pintype "passive"))
      (node (ref "R1") (pin "2") (pinfunction "2_2") (pintype "passive"))
      (node (ref "R3") (pin "1") (pinfunction "1_1") (pintype "passive"))
      (node (ref "U7") (pin "6") (pinfunction "VOUT_6") (pintype "passive"))
    )
    (net (code "71") (name "Net-(U8-+IN)") (class "Default")
      (node (ref "R13") (pin "2") (pinfunction "2_2") (pintype "passive"))
      (node (ref "U8") (pin "3") (pinfunction "+IN_3") (pintype "passive"))
    )
    (net (code "72") (name "Net-(U8-+Vs)") (class "Default")
      (node (ref "C42") (pin "2") (pinfunction "2_2") (pintype "passive"))
      (node (ref "C43") (pin "2") (pinfunction "2_2") (pintype "passive"))
      (node (ref "R18") (pin "1") (pinfunction "1_1") (pintype "passive"))
      (node (ref "U8") (pin "7") (pinfunction "+Vs_7") (pintype "passive"))
    )
    (net (code "73") (name "Net-(U8--IN)") (class "Default")
      (node (ref "C24") (pin "2") (pinfunction "2_2") (pintype "passive"))
      (node (ref "R2") (pin "1") (pinfunction "1_1") (pintype "passive"))
      (node (ref "R6") (pin "2") (pinfunction "2_2") (pintype "passive"))
      (node (ref "U8") (pin "2") (pinfunction "-IN_2") (pintype "passive"))
    )
    (net (code "74") (name "Net-(U8--Vs)") (class "Default")
      (node (ref "C40") (pin "2") (pinfunction "2_2") (pintype "passive"))
      (node (ref "C41") (pin "2") (pinfunction "2_2") (pintype "passive"))
      (node (ref "R17") (pin "2") (pinfunction "2_2") (pintype "passive"))
      (node (ref "U8") (pin "4") (pinfunction "-Vs_4") (pintype "passive"))
    )
    (net (code "75") (name "Net-(U8-VOUT)") (class "Default")
      (node (ref "C24") (pin "1") (pinfunction "1_1") (pintype "passive"))
      (node (ref "R2") (pin "2") (pinfunction "2_2") (pintype "passive"))
      (node (ref "R4") (pin "1") (pinfunction "1_1") (pintype "passive"))
      (node (ref "U8") (pin "6") (pinfunction "VOUT_6") (pintype "passive"))
    )
    (net (code "76") (name "Net-(U9-VIN)") (class "Default")
      (node (ref "C28") (pin "2") (pinfunction "2_2") (pintype "passive"))
      (node (ref "R3") (pin "2") (pinfunction "2_2") (pintype "passive"))
      (node (ref "U9") (pin "3") (pinfunction "VIN_3") (pintype "passive"))
    )
    (net (code "77") (name "Net-(U10-VDD)") (class "Default")
      (node (ref "C51") (pin "2") (pinfunction "2_2") (pintype "passive"))
      (node (ref "C53") (pin "1") (pinfunction "1_1") (pintype "passive"))
      (node (ref "U10") (pin "1") (pinfunction "VDD_1") (pintype "passive"))
      (node (ref "U12") (pin "6") (pinfunction "OUT_6") (pintype "passive"))
    )
    (net (code "78") (name "Net-(U10-VIN)") (class "Default")
      (node (ref "C29") (pin "2") (pinfunction "2_2") (pintype "passive"))
      (node (ref "R4") (pin "2") (pinfunction "2_2") (pintype "passive"))
      (node (ref "U10") (pin "3") (pinfunction "VIN_3") (pintype "passive"))
    )
    (net (code "79") (name "Net-(U11-OUT)") (class "Default")
      (node (ref "C50") (pin "2") (pinfunction "2_2") (pintype "passive"))
      (node (ref "C52") (pin "1") (pinfunction "1_1") (pintype "passive"))
      (node (ref "U11") (pin "6") (pinfunction "OUT_6") (pintype "passive"))
      (node (ref "U9") (pin "1") (pinfunction "VDD_1") (pintype "passive"))
    )
    (net (code "80") (name "Net-(U13-+IN)") (class "Default")
      (node (ref "R33") (pin "2") (pinfunction "2_2") (pintype "passive"))
      (node (ref "U13") (pin "3") (pinfunction "+IN_3") (pintype "passive"))
    )
    (net (code "81") (name "Net-(U13-+Vs)") (class "Default")
      (node (ref "C66") (pin "2") (pinfunction "2_2") (pintype "passive"))
      (node (ref "C67") (pin "2") (pinfunction "2_2") (pintype "passive"))
      (node (ref "R36") (pin "1") (pinfunction "1_1") (pintype "passive"))
      (node (ref "U13") (pin "7") (pinfunction "+Vs_7") (pintype "passive"))
    )
    (net (code "82") (name "Net-(U13--IN)") (class "Default")
      (node (ref "C55") (pin "2") (pinfunction "2_2") (pintype "passive"))
      (node (ref "R22") (pin "1") (pinfunction "1_1") (pintype "passive"))
      (node (ref "R27") (pin "2") (pinfunction "2_2") (pintype "passive"))
      (node (ref "U13") (pin "2") (pinfunction "-IN_2") (pintype "passive"))
    )
    (net (code "83") (name "Net-(U13--Vs)") (class "Default")
      (node (ref "C64") (pin "2") (pinfunction "2_2") (pintype "passive"))
      (node (ref "C65") (pin "2") (pinfunction "2_2") (pintype "passive"))
      (node (ref "R35") (pin "2") (pinfunction "2_2") (pintype "passive"))
      (node (ref "U13") (pin "4") (pinfunction "-Vs_4") (pintype "passive"))
    )
    (net (code "84") (name "Net-(U13-VOUT)") (class "Default")
      (node (ref "C55") (pin "1") (pinfunction "1_1") (pintype "passive"))
      (node (ref "R22") (pin "2") (pinfunction "2_2") (pintype "passive"))
      (node (ref "R25") (pin "1") (pinfunction "1_1") (pintype "passive"))
      (node (ref "U13") (pin "6") (pinfunction "VOUT_6") (pintype "passive"))
    )
    (net (code "85") (name "Net-(U14-+IN)") (class "Default")
      (node (ref "R34") (pin "2") (pinfunction "2_2") (pintype "passive"))
      (node (ref "U14") (pin "3") (pinfunction "+IN_3") (pintype "passive"))
    )
    (net (code "86") (name "Net-(U14-+Vs)") (class "Default")
      (node (ref "C74") (pin "2") (pinfunction "2_2") (pintype "passive"))
      (node (ref "C75") (pin "2") (pinfunction "2_2") (pintype "passive"))
      (node (ref "R38") (pin "1") (pinfunction "1_1") (pintype "passive"))
      (node (ref "U14") (pin "7") (pinfunction "+Vs_7") (pintype "passive"))
    )
    (net (code "87") (name "Net-(U14--IN)") (class "Default")
      (node (ref "C56") (pin "2") (pinfunction "2_2") (pintype "passive"))
      (node (ref "R23") (pin "1") (pinfunction "1_1") (pintype "passive"))
      (node (ref "R28") (pin "2") (pinfunction "2_2") (pintype "passive"))
      (node (ref "U14") (pin "2") (pinfunction "-IN_2") (pintype "passive"))
    )
    (net (code "88") (name "Net-(U14--Vs)") (class "Default")
      (node (ref "C72") (pin "2") (pinfunction "2_2") (pintype "passive"))
      (node (ref "C73") (pin "2") (pinfunction "2_2") (pintype "passive"))
      (node (ref "R37") (pin "2") (pinfunction "2_2") (pintype "passive"))
      (node (ref "U14") (pin "4") (pinfunction "-Vs_4") (pintype "passive"))
    )
    (net (code "89") (name "Net-(U14-VOUT)") (class "Default")
      (node (ref "C56") (pin "1") (pinfunction "1_1") (pintype "passive"))
      (node (ref "R23") (pin "2") (pinfunction "2_2") (pintype "passive"))
      (node (ref "R26") (pin "1") (pinfunction "1_1") (pintype "passive"))
      (node (ref "U14") (pin "6") (pinfunction "VOUT_6") (pintype "passive"))
    )
    (net (code "90") (name "Net-(U15-VDD)") (class "Default")
      (node (ref "C82") (pin "2") (pinfunction "2_2") (pintype "passive"))
      (node (ref "C84") (pin "1") (pinfunction "1_1") (pintype "passive"))
      (node (ref "U15") (pin "1") (pinfunction "VDD_1") (pintype "passive"))
      (node (ref "U17") (pin "6") (pinfunction "OUT_6") (pintype "passive"))
    )
    (net (code "91") (name "Net-(U15-VIN)") (class "Default")
      (node (ref "C59") (pin "2") (pinfunction "2_2") (pintype "passive"))
      (node (ref "R25") (pin "2") (pinfunction "2_2") (pintype "passive"))
      (node (ref "U15") (pin "3") (pinfunction "VIN_3") (pintype "passive"))
    )
    (net (code "92") (name "Net-(U16-VDD)") (class "Default")
      (node (ref "C83") (pin "2") (pinfunction "2_2") (pintype "passive"))
      (node (ref "C85") (pin "1") (pinfunction "1_1") (pintype "passive"))
      (node (ref "U16") (pin "1") (pinfunction "VDD_1") (pintype "passive"))
      (node (ref "U18") (pin "6") (pinfunction "OUT_6") (pintype "passive"))
    )
    (net (code "93") (name "Net-(U16-VIN)") (class "Default")
      (node (ref "C60") (pin "2") (pinfunction "2_2") (pintype "passive"))
      (node (ref "R26") (pin "2") (pinfunction "2_2") (pintype "passive"))
      (node (ref "U16") (pin "3") (pinfunction "VIN_3") (pintype "passive"))
    )
    (net (code "94") (name "Net-(U19-+IN)") (class "Default")
      (node (ref "R54") (pin "2") (pinfunction "2_2") (pintype "passive"))
      (node (ref "U19") (pin "3") (pinfunction "+IN_3") (pintype "passive"))
    )
    (net (code "95") (name "Net-(U19-+Vs)") (class "Default")
      (node (ref "C97") (pin "2") (pinfunction "2_2") (pintype "passive"))
      (node (ref "C98") (pin "2") (pinfunction "2_2") (pintype "passive"))
      (node (ref "R58") (pin "1") (pinfunction "1_1") (pintype "passive"))
      (node (ref "U19") (pin "7") (pinfunction "+Vs_7") (pintype "passive"))
    )
    (net (code "96") (name "Net-(U19--IN)") (class "Default")
      (node (ref "C87") (pin "2") (pinfunction "2_2") (pintype "passive"))
      (node (ref "R43") (pin "1") (pinfunction "1_1") (pintype "passive"))
      (node (ref "R48") (pin "2") (pinfunction "2_2") (pintype "passive"))
      (node (ref "U19") (pin "2") (pinfunction "-IN_2") (pintype "passive"))
    )
    (net (code "97") (name "Net-(U19--Vs)") (class "Default")
      (node (ref "C95") (pin "2") (pinfunction "2_2") (pintype "passive"))
      (node (ref "C96") (pin "2") (pinfunction "2_2") (pintype "passive"))
      (node (ref "R57") (pin "2") (pinfunction "2_2") (pintype "passive"))
      (node (ref "U19") (pin "4") (pinfunction "-Vs_4") (pintype "passive"))
    )
    (net (code "98") (name "Net-(U19-VOUT)") (class "Default")
      (node (ref "C87") (pin "1") (pinfunction "1_1") (pintype "passive"))
      (node (ref "R43") (pin "2") (pinfunction "2_2") (pintype "passive"))
      (node (ref "R46") (pin "1") (pinfunction "1_1") (pintype "passive"))
      (node (ref "U19") (pin "6") (pinfunction "VOUT_6") (pintype "passive"))
    )
    (net (code "99") (name "Net-(U20-+IN)") (class "Default")
      (node (ref "R55") (pin "2") (pinfunction "2_2") (pintype "passive"))
      (node (ref "U20") (pin "3") (pinfunction "+IN_3") (pintype "passive"))
    )
    (net (code "100") (name "Net-(U20-+Vs)") (class "Default")
      (node (ref "C105") (pin "2") (pinfunction "2_2") (pintype "passive"))
      (node (ref "C106") (pin "2") (pinfunction "2_2") (pintype "passive"))
      (node (ref "R60") (pin "1") (pinfunction "1_1") (pintype "passive"))
      (node (ref "U20") (pin "7") (pinfunction "+Vs_7") (pintype "passive"))
    )
    (net (code "101") (name "Net-(U20--IN)") (class "Default")
      (node (ref "C88") (pin "2") (pinfunction "2_2") (pintype "passive"))
      (node (ref "R44") (pin "1") (pinfunction "1_1") (pintype "passive"))
      (node (ref "R49") (pin "2") (pinfunction "2_2") (pintype "passive"))
      (node (ref "U20") (pin "2") (pinfunction "-IN_2") (pintype "passive"))
    )
    (net (code "102") (name "Net-(U20--Vs)") (class "Default")
      (node (ref "C103") (pin "2") (pinfunction "2_2") (pintype "passive"))
      (node (ref "C104") (pin "1") (pinfunction "1_1") (pintype "passive"))
      (node (ref "R59") (pin "2") (pinfunction "2_2") (pintype "passive"))
      (node (ref "U20") (pin "4") (pinfunction "-Vs_4") (pintype "passive"))
    )
    (net (code "103") (name "Net-(U20-VOUT)") (class "Default")
      (node (ref "C88") (pin "1") (pinfunction "1_1") (pintype "passive"))
      (node (ref "R44") (pin "2") (pinfunction "2_2") (pintype "passive"))
      (node (ref "R47") (pin "1") (pinfunction "1_1") (pintype "passive"))
      (node (ref "U20") (pin "6") (pinfunction "VOUT_6") (pintype "passive"))
    )
    (net (code "104") (name "Net-(U21-VDD)") (class "Default")
      (node (ref "C113") (pin "2") (pinfunction "2_2") (pintype "passive"))
      (node (ref "C116") (pin "1") (pinfunction "1_1") (pintype "passive"))
      (node (ref "U21") (pin "1") (pinfunction "VDD_1") (pintype "passive"))
      (node (ref "U23") (pin "6") (pinfunction "OUT_6") (pintype "passive"))
    )
    (net (code "105") (name "Net-(U21-VIN)") (class "Default")
      (node (ref "C91") (pin "2") (pinfunction "2_2") (pintype "passive"))
      (node (ref "R46") (pin "2") (pinfunction "2_2") (pintype "passive"))
      (node (ref "U21") (pin "3") (pinfunction "VIN_3") (pintype "passive"))
    )
    (net (code "106") (name "Net-(U22-VDD)") (class "Default")
      (node (ref "C114") (pin "2") (pinfunction "2_2") (pintype "passive"))
      (node (ref "C117") (pin "1") (pinfunction "1_1") (pintype "passive"))
      (node (ref "U22") (pin "1") (pinfunction "VDD_1") (pintype "passive"))
      (node (ref "U24") (pin "6") (pinfunction "OUT_6") (pintype "passive"))
    )
    (net (code "107") (name "Net-(U22-VIN)") (class "Default")
      (node (ref "C92") (pin "2") (pinfunction "2_2") (pintype "passive"))
      (node (ref "R47") (pin "2") (pinfunction "2_2") (pintype "passive"))
      (node (ref "U22") (pin "3") (pinfunction "VIN_3") (pintype "passive"))
    )
    (net (code "108") (name "Net-(U25-+IN)") (class "Default")
      (node (ref "R70") (pin "2") (pinfunction "2_2") (pintype "passive"))
      (node (ref "U25") (pin "3") (pinfunction "+IN_3") (pintype "passive"))
    )
    (net (code "109") (name "Net-(U25-+Vs)") (class "Default")
      (node (ref "C126") (pin "2") (pinfunction "2_2") (pintype "passive"))
      (node (ref "C127") (pin "2") (pinfunction "2_2") (pintype "passive"))
      (node (ref "R73") (pin "1") (pinfunction "1_1") (pintype "passive"))
      (node (ref "U25") (pin "7") (pinfunction "+Vs_7") (pintype "passive"))
    )
    (net (code "110") (name "Net-(U25--IN)") (class "Default")
      (node (ref "C118") (pin "2") (pinfunction "2_2") (pintype "passive"))
      (node (ref "R64") (pin "1") (pinfunction "1_1") (pintype "passive"))
      (node (ref "R66") (pin "2") (pinfunction "2_2") (pintype "passive"))
      (node (ref "U25") (pin "2") (pinfunction "-IN_2") (pintype "passive"))
    )
    (net (code "111") (name "Net-(U25--Vs)") (class "Default")
      (node (ref "C124") (pin "2") (pinfunction "2_2") (pintype "passive"))
      (node (ref "C125") (pin "2") (pinfunction "2_2") (pintype "passive"))
      (node (ref "R72") (pin "2") (pinfunction "2_2") (pintype "passive"))
      (node (ref "U25") (pin "4") (pinfunction "-Vs_4") (pintype "passive"))
    )
    (net (code "112") (name "Net-(U25-VOUT)") (class "Default")
      (node (ref "C118") (pin "1") (pinfunction "1_1") (pintype "passive"))
      (node (ref "R64") (pin "2") (pinfunction "2_2") (pintype "passive"))
      (node (ref "R65") (pin "1") (pinfunction "1_1") (pintype "passive"))
      (node (ref "U25") (pin "6") (pinfunction "VOUT_6") (pintype "passive"))
    )
    (net (code "113") (name "Net-(U26-VDD)") (class "Default")
      (node (ref "C132") (pin "2") (pinfunction "2_2") (pintype "passive"))
      (node (ref "C133") (pin "1") (pinfunction "1_1") (pintype "passive"))
      (node (ref "U26") (pin "1") (pinfunction "VDD_1") (pintype "passive"))
      (node (ref "U27") (pin "6") (pinfunction "OUT_6") (pintype "passive"))
    )
    (net (code "114") (name "Net-(U26-VIN)") (class "Default")
      (node (ref "C121") (pin "2") (pinfunction "2_2") (pintype "passive"))
      (node (ref "R65") (pin "2") (pinfunction "2_2") (pintype "passive"))
      (node (ref "U26") (pin "3") (pinfunction "VIN_3") (pintype "passive"))
    )
    (net (code "115") (name "Net-(U28-+IN)") (class "Default")
      (node (ref "R83") (pin "2") (pinfunction "2_2") (pintype "passive"))
      (node (ref "U28") (pin "3") (pinfunction "+IN_3") (pintype "passive"))
    )
    (net (code "116") (name "Net-(U28-+Vs)") (class "Default")
      (node (ref "C143") (pin "2") (pinfunction "2_2") (pintype "passive"))
      (node (ref "C144") (pin "2") (pinfunction "2_2") (pintype "passive"))
      (node (ref "R85") (pin "1") (pinfunction "1_1") (pintype "passive"))
      (node (ref "U28") (pin "7") (pinfunction "+Vs_7") (pintype "passive"))
    )
    (net (code "117") (name "Net-(U28--IN)") (class "Default")
      (node (ref "C135") (pin "2") (pinfunction "2_2") (pintype "passive"))
      (node (ref "R77") (pin "1") (pinfunction "1_1") (pintype "passive"))
      (node (ref "R80") (pin "2") (pinfunction "2_2") (pintype "passive"))
      (node (ref "U28") (pin "2") (pinfunction "-IN_2") (pintype "passive"))
    )
    (net (code "118") (name "Net-(U28--Vs)") (class "Default")
      (node (ref "C141") (pin "2") (pinfunction "2_2") (pintype "passive"))
      (node (ref "C142") (pin "2") (pinfunction "2_2") (pintype "passive"))
      (node (ref "R84") (pin "2") (pinfunction "2_2") (pintype "passive"))
      (node (ref "U28") (pin "4") (pinfunction "-Vs_4") (pintype "passive"))
    )
    (net (code "119") (name "Net-(U28-VOUT)") (class "Default")
      (node (ref "C135") (pin "1") (pinfunction "1_1") (pintype "passive"))
      (node (ref "R77") (pin "2") (pinfunction "2_2") (pintype "passive"))
      (node (ref "R79") (pin "1") (pinfunction "1_1") (pintype "passive"))
      (node (ref "U28") (pin "6") (pinfunction "VOUT_6") (pintype "passive"))
    )
    (net (code "120") (name "Net-(U29A-IN+)") (class "Default")
      (node (ref "R87") (pin "1") (pinfunction "1_1") (pintype "passive"))
      (node (ref "R89") (pin "2") (pinfunction "2_2") (pintype "passive"))
      (node (ref "U29") (pin "3") (pinfunction "IN+_3") (pintype "input"))
      (node (ref "U29") (pin "5") (pinfunction "IN+_5") (pintype "input"))
    )
    (net (code "121") (name "Net-(U30-VDD)") (class "Default")
      (node (ref "C155") (pin "2") (pinfunction "2_2") (pintype "passive"))
      (node (ref "C156") (pin "1") (pinfunction "1_1") (pintype "passive"))
      (node (ref "U30") (pin "1") (pinfunction "VDD_1") (pintype "passive"))
      (node (ref "U32") (pin "6") (pinfunction "OUT_6") (pintype "passive"))
    )
    (net (code "122") (name "Net-(U30-VIN)") (class "Default")
      (node (ref "C137") (pin "2") (pinfunction "2_2") (pintype "passive"))
      (node (ref "R79") (pin "2") (pinfunction "2_2") (pintype "passive"))
      (node (ref "U30") (pin "3") (pinfunction "VIN_3") (pintype "passive"))
    )
    (net (code "123") (name "Net-(U31-OUT)") (class "Default")
      (node (ref "C149") (pin "1") (pinfunction "1_1") (pintype "passive"))
      (node (ref "C150") (pin "2") (pinfunction "2_2") (pintype "passive"))
      (node (ref "R87") (pin "2") (pinfunction "2_2") (pintype "passive"))
      (node (ref "U31") (pin "6") (pinfunction "OUT_6") (pintype "passive"))
    )
    (net (code "124") (name "VCC+5V") (class "Default")
      (node (ref "C100") (pin "2") (pinfunction "2_2") (pintype "passive"))
      (node (ref "C107") (pin "2") (pinfunction "2_2") (pintype "passive"))
      (node (ref "C108") (pin "2") (pinfunction "2_2") (pintype "passive"))
      (node (ref "C109") (pin "2") (pinfunction "2_2") (pintype "passive"))
      (node (ref "C110") (pin "2") (pinfunction "2_2") (pintype "passive"))
      (node (ref "C111") (pin "2") (pinfunction "2_2") (pintype "passive"))
      (node (ref "C112") (pin "2") (pinfunction "2_2") (pintype "passive"))
      (node (ref "C115") (pin "2") (pinfunction "2_2") (pintype "passive"))
      (node (ref "C119") (pin "2") (pinfunction "2_2") (pintype "passive"))
      (node (ref "C128") (pin "2") (pinfunction "2_2") (pintype "passive"))
      (node (ref "C129") (pin "2") (pinfunction "2_2") (pintype "passive"))
      (node (ref "C130") (pin "2") (pinfunction "2_2") (pintype "passive"))
      (node (ref "C131") (pin "2") (pinfunction "2_2") (pintype "passive"))
      (node (ref "C134") (pin "2") (pinfunction "2_2") (pintype "passive"))
      (node (ref "C138") (pin "2") (pinfunction "2_2") (pintype "passive"))
      (node (ref "C145") (pin "2") (pinfunction "2_2") (pintype "passive"))
      (node (ref "C146") (pin "2") (pinfunction "2_2") (pintype "passive"))
      (node (ref "C147") (pin "2") (pinfunction "2_2") (pintype "passive"))
      (node (ref "C148") (pin "2") (pinfunction "2_2") (pintype "passive"))
      (node (ref "C151") (pin "2") (pinfunction "2_2") (pintype "passive"))
      (node (ref "C152") (pin "2") (pinfunction "2_2") (pintype "passive"))
      (node (ref "C153") (pin "2") (pinfunction "2_2") (pintype "passive"))
      (node (ref "C154") (pin "2") (pinfunction "2_2") (pintype "passive"))
      (node (ref "C25") (pin "2") (pinfunction "2_2") (pintype "passive"))
      (node (ref "C36") (pin "2") (pinfunction "2_2") (pintype "passive"))
      (node (ref "C37") (pin "2") (pinfunction "2_2") (pintype "passive"))
      (node (ref "C44") (pin "2") (pinfunction "2_2") (pintype "passive"))
      (node (ref "C45") (pin "2") (pinfunction "2_2") (pintype "passive"))
      (node (ref "C46") (pin "2") (pinfunction "2_2") (pintype "passive"))
      (node (ref "C47") (pin "2") (pinfunction "2_2") (pintype "passive"))
      (node (ref "C48") (pin "2") (pinfunction "2_2") (pintype "passive"))
      (node (ref "C49") (pin "2") (pinfunction "2_2") (pintype "passive"))
      (node (ref "C54") (pin "2") (pinfunction "2_2") (pintype "passive"))
      (node (ref "C61") (pin "2") (pinfunction "2_2") (pintype "passive"))
      (node (ref "C68") (pin "2") (pinfunction "2_2") (pintype "passive"))
      (node (ref "C69") (pin "2") (pinfunction "2_2") (pintype "passive"))
      (node (ref "C76") (pin "2") (pinfunction "2_2") (pintype "passive"))
      (node (ref "C77") (pin "2") (pinfunction "2_2") (pintype "passive"))
      (node (ref "C78") (pin "2") (pinfunction "2_2") (pintype "passive"))
      (node (ref "C79") (pin "2") (pinfunction "2_2") (pintype "passive"))
      (node (ref "C80") (pin "2") (pinfunction "2_2") (pintype "passive"))
      (node (ref "C81") (pin "2") (pinfunction "2_2") (pintype "passive"))
      (node (ref "C86") (pin "2") (pinfunction "2_2") (pintype "passive"))
      (node (ref "C99") (pin "2") (pinfunction "2_2") (pintype "passive"))
      (node (ref "Q1") (pin "2") (pinfunction "E_2") (pintype "passive"))
      (node (ref "Q2") (pin "2") (pinfunction "E_2") (pintype "passive"))
      (node (ref "Q3") (pin "2") (pinfunction "E_2") (pintype "passive"))
      (node (ref "Q4") (pin "2") (pinfunction "E_2") (pintype "passive"))
      (node (ref "Q5") (pin "2") (pinfunction "E_2") (pintype "passive"))
      (node (ref "Q6") (pin "2") (pinfunction "E_2") (pintype "passive"))
      (node (ref "Q7") (pin "2") (pinfunction "E_2") (pintype "passive"))
      (node (ref "Q8") (pin "2") (pinfunction "E_2") (pintype "passive"))
      (node (ref "R11") (pin "2") (pinfunction "2_2") (pintype "passive"))
      (node (ref "R16") (pin "2") (pinfunction "2_2") (pintype "passive"))
      (node (ref "R18") (pin "2") (pinfunction "2_2") (pintype "passive"))
      (node (ref "R20") (pin "2") (pinfunction "2_2") (pintype "passive"))
      (node (ref "R36") (pin "2") (pinfunction "2_2") (pintype "passive"))
      (node (ref "R38") (pin "2") (pinfunction "2_2") (pintype "passive"))
      (node (ref "R39") (pin "2") (pinfunction "2_2") (pintype "passive"))
      (node (ref "R42") (pin "2") (pinfunction "2_2") (pintype "passive"))
      (node (ref "R58") (pin "2") (pinfunction "2_2") (pintype "passive"))
      (node (ref "R60") (pin "2") (pinfunction "2_2") (pintype "passive"))
      (node (ref "R61") (pin "2") (pinfunction "2_2") (pintype "passive"))
      (node (ref "R67") (pin "2") (pinfunction "2_2") (pintype "passive"))
      (node (ref "R73") (pin "2") (pinfunction "2_2") (pintype "passive"))
      (node (ref "R75") (pin "2") (pinfunction "2_2") (pintype "passive"))
      (node (ref "R85") (pin "2") (pinfunction "2_2") (pintype "passive"))
      (node (ref "R86") (pin "2") (pinfunction "2_2") (pintype "passive"))
      (node (ref "U11") (pin "2") (pinfunction "+Vs_2") (pintype "passive"))
      (node (ref "U12") (pin "2") (pinfunction "+Vs_2") (pintype "passive"))
      (node (ref "U17") (pin "2") (pinfunction "+Vs_2") (pintype "passive"))
      (node (ref "U18") (pin "2") (pinfunction "+Vs_2") (pintype "passive"))
      (node (ref "U23") (pin "2") (pinfunction "+Vs_2") (pintype "passive"))
      (node (ref "U24") (pin "2") (pinfunction "+Vs_2") (pintype "passive"))
      (node (ref "U27") (pin "2") (pinfunction "+Vs_2") (pintype "passive"))
      (node (ref "U29") (pin "8") (pinfunction "V+_8") (pintype "power_in"))
      (node (ref "U31") (pin "2") (pinfunction "+Vs_2") (pintype "passive"))
      (node (ref "U32") (pin "2") (pinfunction "+Vs_2") (pintype "passive"))
    )
    (net (code "125") (name "VCC+24V") (class "Default")
      (node (ref "P1") (pin "10") (pinfunction "10_10") (pintype "passive"))
      (node (ref "P1") (pin "9") (pinfunction "9_9") (pintype "passive"))
    )
    (net (code "126") (name "VCC-5V") (class "Default")
      (node (ref "C101") (pin "2") (pinfunction "2_2") (pintype "passive"))
      (node (ref "C102") (pin "2") (pinfunction "2_2") (pintype "passive"))
      (node (ref "C122") (pin "2") (pinfunction "2_2") (pintype "passive"))
      (node (ref "C123") (pin "2") (pinfunction "2_2") (pintype "passive"))
      (node (ref "C139") (pin "2") (pinfunction "2_2") (pintype "passive"))
      (node (ref "C140") (pin "2") (pinfunction "2_2") (pintype "passive"))
      (node (ref "C30") (pin "2") (pinfunction "2_2") (pintype "passive"))
      (node (ref "C31") (pin "2") (pinfunction "2_2") (pintype "passive"))
      (node (ref "C38") (pin "2") (pinfunction "2_2") (pintype "passive"))
      (node (ref "C39") (pin "2") (pinfunction "2_2") (pintype "passive"))
      (node (ref "C62") (pin "2") (pinfunction "2_2") (pintype "passive"))
      (node (ref "C63") (pin "2") (pinfunction "2_2") (pintype "passive"))
      (node (ref "C70") (pin "2") (pinfunction "2_2") (pintype "passive"))
      (node (ref "C71") (pin "2") (pinfunction "2_2") (pintype "passive"))
      (node (ref "C93") (pin "2") (pinfunction "2_2") (pintype "passive"))
      (node (ref "C94") (pin "2") (pinfunction "2_2") (pintype "passive"))
      (node (ref "R15") (pin "1") (pinfunction "1_1") (pintype "passive"))
      (node (ref "R17") (pin "1") (pinfunction "1_1") (pintype "passive"))
      (node (ref "R35") (pin "1") (pinfunction "1_1") (pintype "passive"))
      (node (ref "R37") (pin "1") (pinfunction "1_1") (pintype "passive"))
      (node (ref "R57") (pin "1") (pinfunction "1_1") (pintype "passive"))
      (node (ref "R59") (pin "1") (pinfunction "1_1") (pintype "passive"))
      (node (ref "R72") (pin "1") (pinfunction "1_1") (pintype "passive"))
      (node (ref "R84") (pin "1") (pinfunction "1_1") (pintype "passive"))
    )
    (net (code "127") (name "VREF1+1.3V") (class "Default")
      (node (ref "R12") (pin "1") (pinfunction "1_1") (pintype "passive"))
      (node (ref "R33") (pin "1") (pinfunction "1_1") (pintype "passive"))
      (node (ref "R54") (pin "1") (pinfunction "1_1") (pintype "passive"))
      (node (ref "R70") (pin "1") (pinfunction "1_1") (pintype "passive"))
      (node (ref "U29") (pin "1") (pinfunction "OUT_1") (pintype "output"))
      (node (ref "U29") (pin "2") (pinfunction "IN-_2") (pintype "input"))
    )
    (net (code "128") (name "VREF2+1.3V") (class "Default")
      (node (ref "R13") (pin "1") (pinfunction "1_1") (pintype "passive"))
      (node (ref "R34") (pin "1") (pinfunction "1_1") (pintype "passive"))
      (node (ref "R55") (pin "1") (pinfunction "1_1") (pintype "passive"))
      (node (ref "R83") (pin "1") (pinfunction "1_1") (pintype "passive"))
      (node (ref "U29") (pin "6") (pinfunction "IN-_6") (pintype "input"))
      (node (ref "U29") (pin "7") (pinfunction "OUT_7") (pintype "output"))
    )
    (net (code "129") (name "unconnected-(U7-NC-Pad1)") (class "Default")
      (node (ref "U7") (pin "1") (pinfunction "NC_1") (pintype "passive"))
    )
    (net (code "130") (name "unconnected-(U7-NC-Pad5)") (class "Default")
      (node (ref "U7") (pin "5") (pinfunction "NC_5") (pintype "passive"))
    )
    (net (code "131") (name "unconnected-(U7-~{DIS}{slash}SEL-Pad8)") (class "Default")
      (node (ref "U7") (pin "8") (pinfunction "~{DIS}/SEL_8") (pintype "passive"))
    )
    (net (code "132") (name "unconnected-(U8-NC-Pad1)") (class "Default")
      (node (ref "U8") (pin "1") (pinfunction "NC_1") (pintype "passive"))
    )
    (net (code "133") (name "unconnected-(U8-NC-Pad5)") (class "Default")
      (node (ref "U8") (pin "5") (pinfunction "NC_5") (pintype "passive"))
    )
    (net (code "134") (name "unconnected-(U8-~{DIS}{slash}SEL-Pad8)") (class "Default")
      (node (ref "U8") (pin "8") (pinfunction "~{DIS}/SEL_8") (pintype "passive"))
    )
    (net (code "135") (name "unconnected-(U11-NC-Pad7)") (class "Default")
      (node (ref "U11") (pin "7") (pinfunction "NC_7") (pintype "passive"))
    )
    (net (code "136") (name "unconnected-(U11-NC-Pad8)") (class "Default")
      (node (ref "U11") (pin "8") (pinfunction "NC_8") (pintype "passive"))
    )
    (net (code "137") (name "unconnected-(U11-TP-Pad1)") (class "Default")
      (node (ref "U11") (pin "1") (pinfunction "TP_1") (pintype "passive"))
    )
    (net (code "138") (name "unconnected-(U11-TP-Pad5)") (class "Default")
      (node (ref "U11") (pin "5") (pinfunction "TP_5") (pintype "passive"))
    )
    (net (code "139") (name "unconnected-(U11-~{SLEEP}-Pad3)") (class "Default")
      (node (ref "U11") (pin "3") (pinfunction "~{SLEEP}_3") (pintype "passive"))
    )
    (net (code "140") (name "unconnected-(U12-NC-Pad7)") (class "Default")
      (node (ref "U12") (pin "7") (pinfunction "NC_7") (pintype "passive"))
    )
    (net (code "141") (name "unconnected-(U12-NC-Pad8)") (class "Default")
      (node (ref "U12") (pin "8") (pinfunction "NC_8") (pintype "passive"))
    )
    (net (code "142") (name "unconnected-(U12-TP-Pad1)") (class "Default")
      (node (ref "U12") (pin "1") (pinfunction "TP_1") (pintype "passive"))
    )
    (net (code "143") (name "unconnected-(U12-TP-Pad5)") (class "Default")
      (node (ref "U12") (pin "5") (pinfunction "TP_5") (pintype "passive"))
    )
    (net (code "144") (name "unconnected-(U12-~{SLEEP}-Pad3)") (class "Default")
      (node (ref "U12") (pin "3") (pinfunction "~{SLEEP}_3") (pintype "passive"))
    )
    (net (code "145") (name "unconnected-(U13-NC-Pad1)") (class "Default")
      (node (ref "U13") (pin "1") (pinfunction "NC_1") (pintype "passive"))
    )
    (net (code "146") (name "unconnected-(U13-NC-Pad5)") (class "Default")
      (node (ref "U13") (pin "5") (pinfunction "NC_5") (pintype "passive"))
    )
    (net (code "147") (name "unconnected-(U13-~{DIS}{slash}SEL-Pad8)") (class "Default")
      (node (ref "U13") (pin "8") (pinfunction "~{DIS}/SEL_8") (pintype "passive"))
    )
    (net (code "148") (name "unconnected-(U14-NC-Pad1)") (class "Default")
      (node (ref "U14") (pin "1") (pinfunction "NC_1") (pintype "passive"))
    )
    (net (code "149") (name "unconnected-(U14-NC-Pad5)") (class "Default")
      (node (ref "U14") (pin "5") (pinfunction "NC_5") (pintype "passive"))
    )
    (net (code "150") (name "unconnected-(U14-~{DIS}{slash}SEL-Pad8)") (class "Default")
      (node (ref "U14") (pin "8") (pinfunction "~{DIS}/SEL_8") (pintype "passive"))
    )
    (net (code "151") (name "unconnected-(U17-NC-Pad7)") (class "Default")
      (node (ref "U17") (pin "7") (pinfunction "NC_7") (pintype "passive"))
    )
    (net (code "152") (name "unconnected-(U17-NC-Pad8)") (class "Default")
      (node (ref "U17") (pin "8") (pinfunction "NC_8") (pintype "passive"))
    )
    (net (code "153") (name "unconnected-(U17-TP-Pad1)") (class "Default")
      (node (ref "U17") (pin "1") (pinfunction "TP_1") (pintype "passive"))
    )
    (net (code "154") (name "unconnected-(U17-TP-Pad5)") (class "Default")
      (node (ref "U17") (pin "5") (pinfunction "TP_5") (pintype "passive"))
    )
    (net (code "155") (name "unconnected-(U17-~{SLEEP}-Pad3)") (class "Default")
      (node (ref "U17") (pin "3") (pinfunction "~{SLEEP}_3") (pintype "passive"))
    )
    (net (code "156") (name "unconnected-(U18-NC-Pad7)") (class "Default")
      (node (ref "U18") (pin "7") (pinfunction "NC_7") (pintype "passive"))
    )
    (net (code "157") (name "unconnected-(U18-NC-Pad8)") (class "Default")
      (node (ref "U18") (pin "8") (pinfunction "NC_8") (pintype "passive"))
    )
    (net (code "158") (name "unconnected-(U18-TP-Pad1)") (class "Default")
      (node (ref "U18") (pin "1") (pinfunction "TP_1") (pintype "passive"))
    )
    (net (code "159") (name "unconnected-(U18-TP-Pad5)") (class "Default")
      (node (ref "U18") (pin "5") (pinfunction "TP_5") (pintype "passive"))
    )
    (net (code "160") (name "unconnected-(U18-~{SLEEP}-Pad3)") (class "Default")
      (node (ref "U18") (pin "3") (pinfunction "~{SLEEP}_3") (pintype "passive"))
    )
    (net (code "161") (name "unconnected-(U19-NC-Pad1)") (class "Default")
      (node (ref "U19") (pin "1") (pinfunction "NC_1") (pintype "passive"))
    )
    (net (code "162") (name "unconnected-(U19-NC-Pad5)") (class "Default")
      (node (ref "U19") (pin "5") (pinfunction "NC_5") (pintype "passive"))
    )
    (net (code "163") (name "unconnected-(U19-~{DIS}{slash}SEL-Pad8)") (class "Default")
      (node (ref "U19") (pin "8") (pinfunction "~{DIS}/SEL_8") (pintype "passive"))
    )
    (net (code "164") (name "unconnected-(U20-NC-Pad1)") (class "Default")
      (node (ref "U20") (pin "1") (pinfunction "NC_1") (pintype "passive"))
    )
    (net (code "165") (name "unconnected-(U20-NC-Pad5)") (class "Default")
      (node (ref "U20") (pin "5") (pinfunction "NC_5") (pintype "passive"))
    )
    (net (code "166") (name "unconnected-(U20-~{DIS}{slash}SEL-Pad8)") (class "Default")
      (node (ref "U20") (pin "8") (pinfunction "~{DIS}/SEL_8") (pintype "passive"))
    )
    (net (code "167") (name "unconnected-(U23-NC-Pad7)") (class "Default")
      (node (ref "U23") (pin "7") (pinfunction "NC_7") (pintype "passive"))
    )
    (net (code "168") (name "unconnected-(U23-NC-Pad8)") (class "Default")
      (node (ref "U23") (pin "8") (pinfunction "NC_8") (pintype "passive"))
    )
    (net (code "169") (name "unconnected-(U23-TP-Pad1)") (class "Default")
      (node (ref "U23") (pin "1") (pinfunction "TP_1") (pintype "passive"))
    )
    (net (code "170") (name "unconnected-(U23-TP-Pad5)") (class "Default")
      (node (ref "U23") (pin "5") (pinfunction "TP_5") (pintype "passive"))
    )
    (net (code "171") (name "unconnected-(U23-~{SLEEP}-Pad3)") (class "Default")
      (node (ref "U23") (pin "3") (pinfunction "~{SLEEP}_3") (pintype "passive"))
    )
    (net (code "172") (name "unconnected-(U24-NC-Pad7)") (class "Default")
      (node (ref "U24") (pin "7") (pinfunction "NC_7") (pintype "passive"))
    )
    (net (code "173") (name "unconnected-(U24-NC-Pad8)") (class "Default")
      (node (ref "U24") (pin "8") (pinfunction "NC_8") (pintype "passive"))
    )
    (net (code "174") (name "unconnected-(U24-TP-Pad1)") (class "Default")
      (node (ref "U24") (pin "1") (pinfunction "TP_1") (pintype "passive"))
    )
    (net (code "175") (name "unconnected-(U24-TP-Pad5)") (class "Default")
      (node (ref "U24") (pin "5") (pinfunction "TP_5") (pintype "passive"))
    )
    (net (code "176") (name "unconnected-(U24-~{SLEEP}-Pad3)") (class "Default")
      (node (ref "U24") (pin "3") (pinfunction "~{SLEEP}_3") (pintype "passive"))
    )
    (net (code "177") (name "unconnected-(U25-NC-Pad1)") (class "Default")
      (node (ref "U25") (pin "1") (pinfunction "NC_1") (pintype "passive"))
    )
    (net (code "178") (name "unconnected-(U25-NC-Pad5)") (class "Default")
      (node (ref "U25") (pin "5") (pinfunction "NC_5") (pintype "passive"))
    )
    (net (code "179") (name "unconnected-(U25-~{DIS}{slash}SEL-Pad8)") (class "Default")
      (node (ref "U25") (pin "8") (pinfunction "~{DIS}/SEL_8") (pintype "passive"))
    )
    (net (code "180") (name "unconnected-(U27-NC-Pad7)") (class "Default")
      (node (ref "U27") (pin "7") (pinfunction "NC_7") (pintype "passive"))
    )
    (net (code "181") (name "unconnected-(U27-NC-Pad8)") (class "Default")
      (node (ref "U27") (pin "8") (pinfunction "NC_8") (pintype "passive"))
    )
    (net (code "182") (name "unconnected-(U27-TP-Pad1)") (class "Default")
      (node (ref "U27") (pin "1") (pinfunction "TP_1") (pintype "passive"))
    )
    (net (code "183") (name "unconnected-(U27-TP-Pad5)") (class "Default")
      (node (ref "U27") (pin "5") (pinfunction "TP_5") (pintype "passive"))
    )
    (net (code "184") (name "unconnected-(U27-~{SLEEP}-Pad3)") (class "Default")
      (node (ref "U27") (pin "3") (pinfunction "~{SLEEP}_3") (pintype "passive"))
    )
    (net (code "185") (name "unconnected-(U28-NC-Pad1)") (class "Default")
      (node (ref "U28") (pin "1") (pinfunction "NC_1") (pintype "passive"))
    )
    (net (code "186") (name "unconnected-(U28-NC-Pad5)") (class "Default")
      (node (ref "U28") (pin "5") (pinfunction "NC_5") (pintype "passive"))
    )
    (net (code "187") (name "unconnected-(U28-~{DIS}{slash}SEL-Pad8)") (class "Default")
      (node (ref "U28") (pin "8") (pinfunction "~{DIS}/SEL_8") (pintype "passive"))
    )
    (net (code "188") (name "unconnected-(U31-NC-Pad7)") (class "Default")
      (node (ref "U31") (pin "7") (pinfunction "NC_7") (pintype "passive"))
    )
    (net (code "189") (name "unconnected-(U31-NC-Pad8)") (class "Default")
      (node (ref "U31") (pin "8") (pinfunction "NC_8") (pintype "passive"))
    )
    (net (code "190") (name "unconnected-(U31-TP-Pad1)") (class "Default")
      (node (ref "U31") (pin "1") (pinfunction "TP_1") (pintype "passive"))
    )
    (net (code "191") (name "unconnected-(U31-TP-Pad5)") (class "Default")
      (node (ref "U31") (pin "5") (pinfunction "TP_5") (pintype "passive"))
    )
    (net (code "192") (name "unconnected-(U31-~{SLEEP}-Pad3)") (class "Default")
      (node (ref "U31") (pin "3") (pinfunction "~{SLEEP}_3") (pintype "passive"))
    )
    (net (code "193") (name "unconnected-(U32-NC-Pad7)") (class "Default")
      (node (ref "U32") (pin "7") (pinfunction "NC_7") (pintype "passive"))
    )
    (net (code "194") (name "unconnected-(U32-NC-Pad8)") (class "Default")
      (node (ref "U32") (pin "8") (pinfunction "NC_8") (pintype "passive"))
    )
    (net (code "195") (name "unconnected-(U32-TP-Pad1)") (class "Default")
      (node (ref "U32") (pin "1") (pinfunction "TP_1") (pintype "passive"))
    )
    (net (code "196") (name "unconnected-(U32-TP-Pad5)") (class "Default")
      (node (ref "U32") (pin "5") (pinfunction "TP_5") (pintype "passive"))
    )
    (net (code "197") (name "unconnected-(U32-~{SLEEP}-Pad3)") (class "Default")
      (node (ref "U32") (pin "3") (pinfunction "~{SLEEP}_3") (pintype "passive"))
    )
  )
)
